# untitled.net
KiCad netlist of a schematic drawn in EAGLE
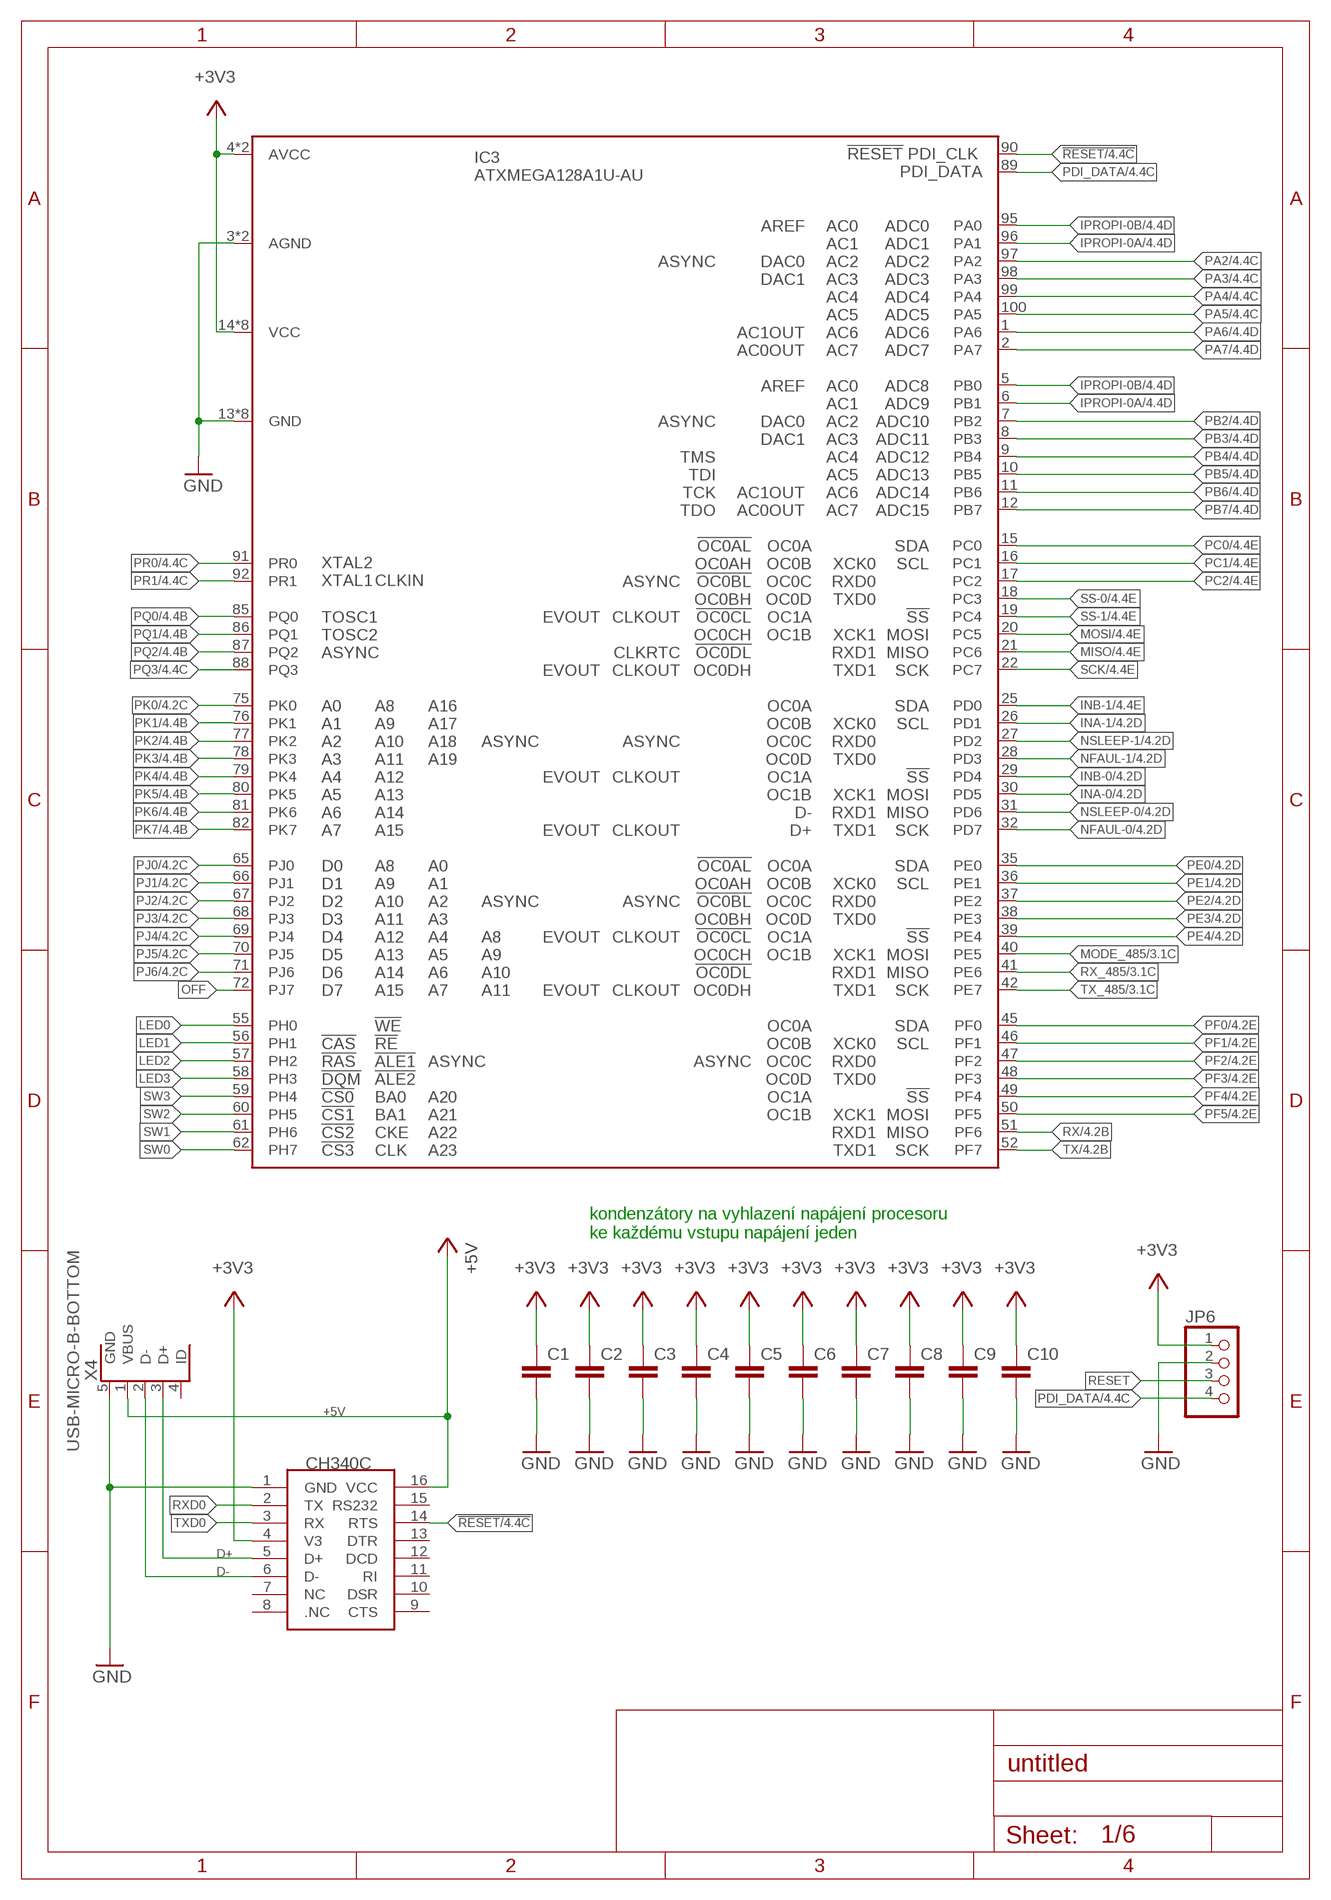
[diagram p0: schematic, sheet 1]
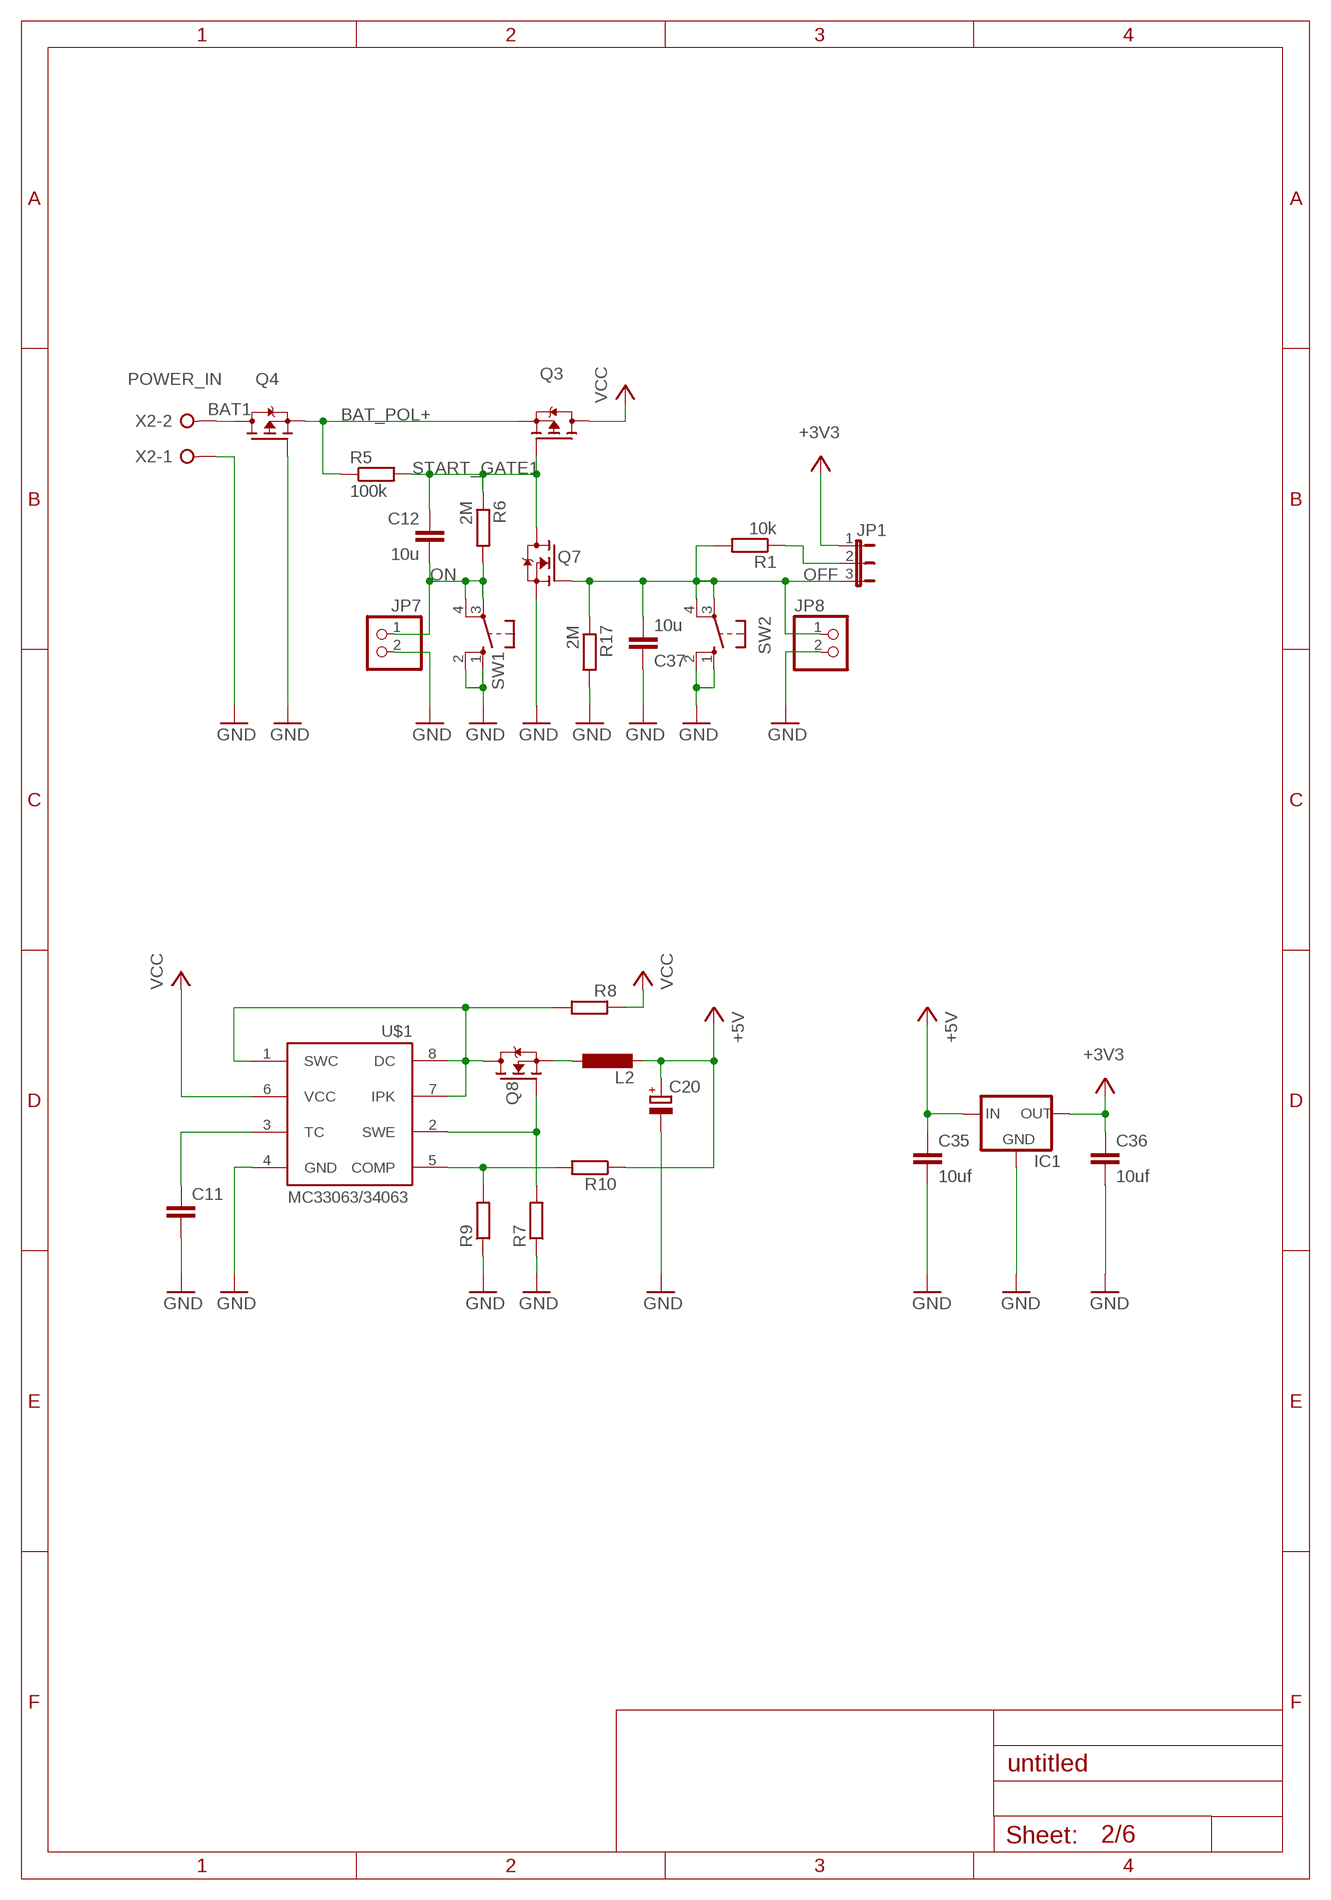
[diagram p1: schematic, sheet 2]
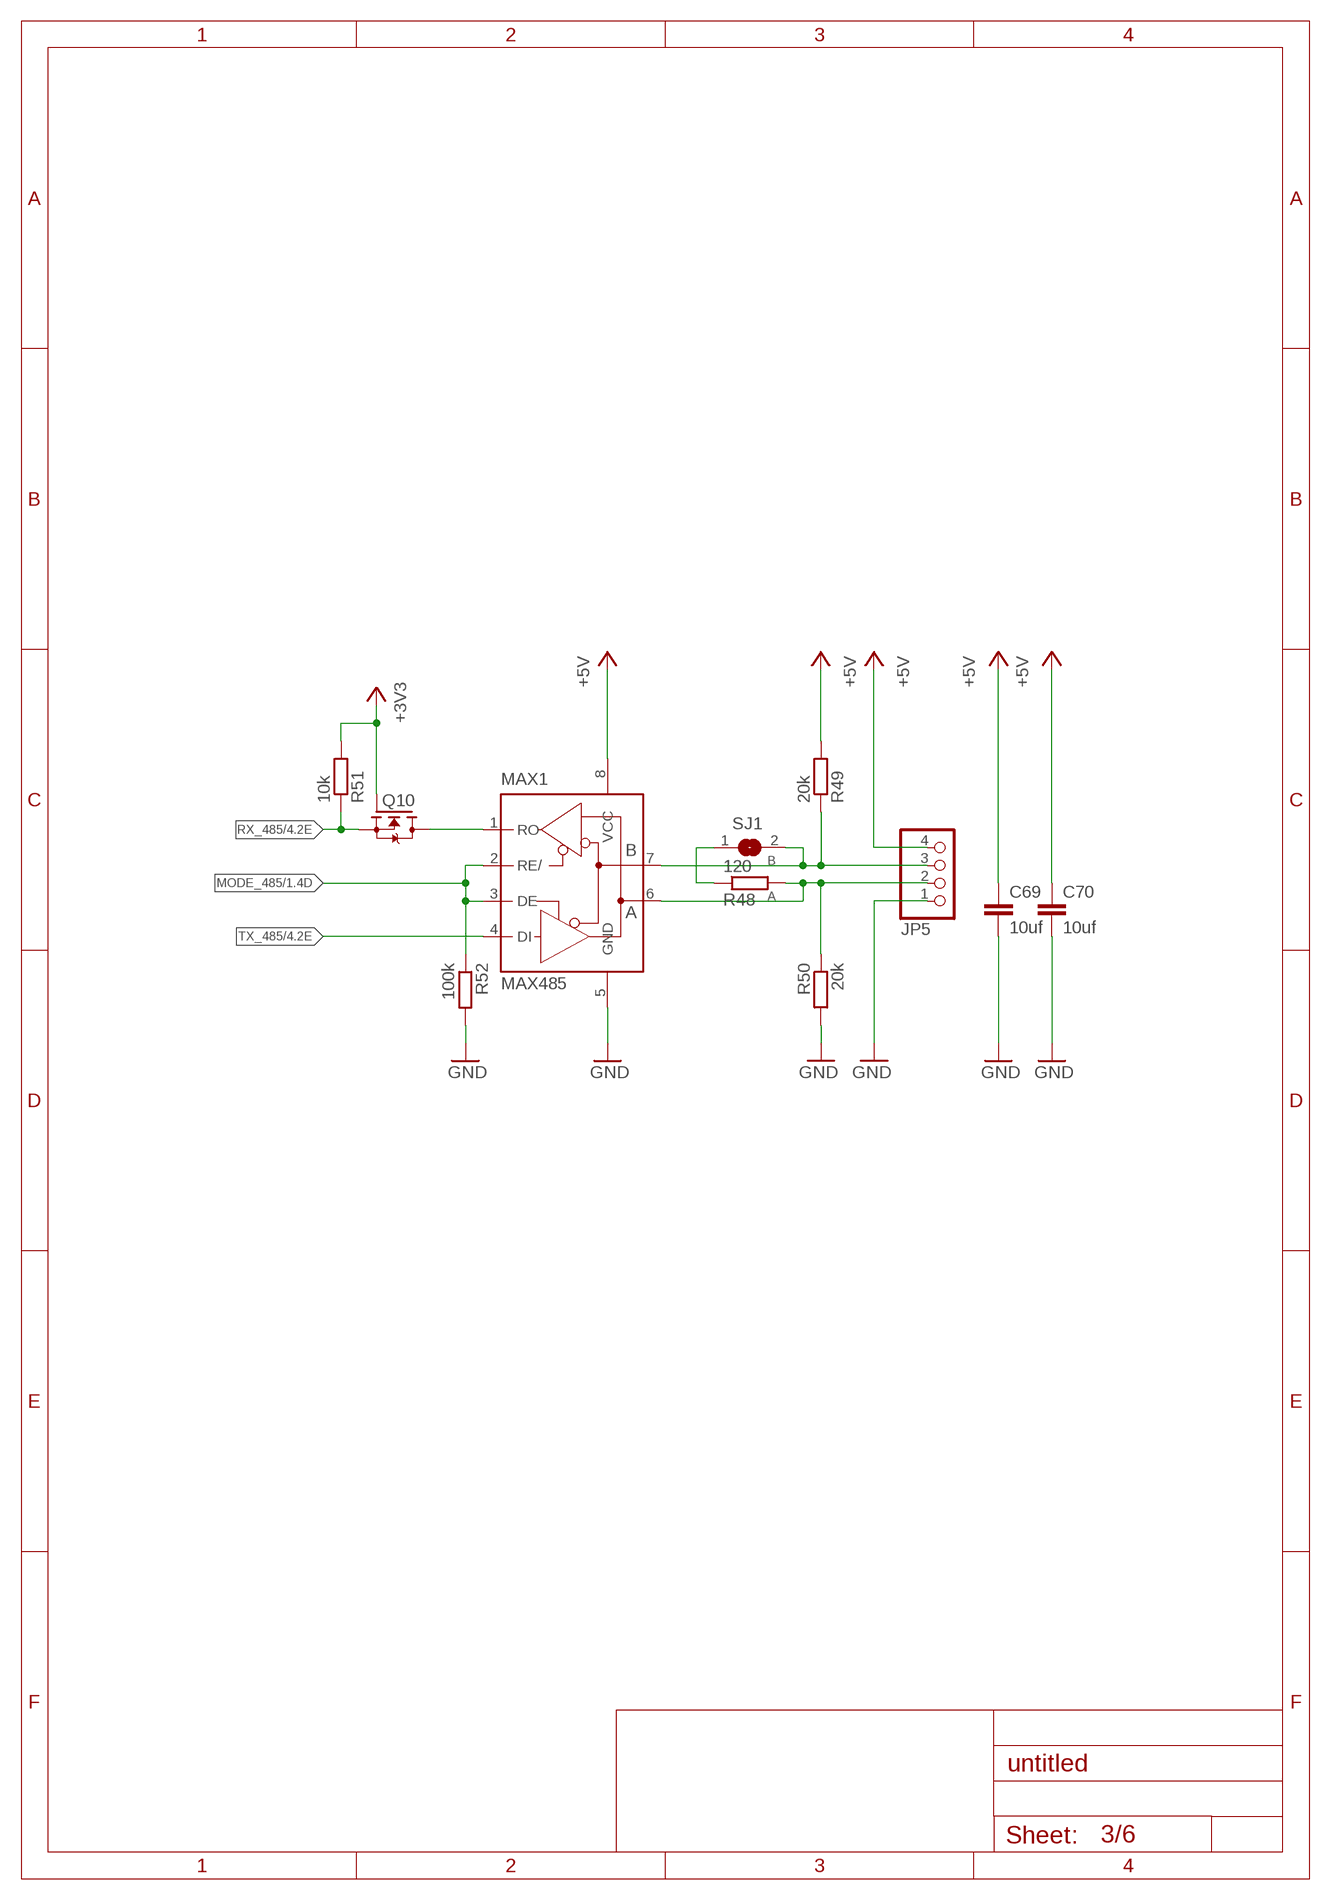
[diagram p2: schematic, sheet 3]
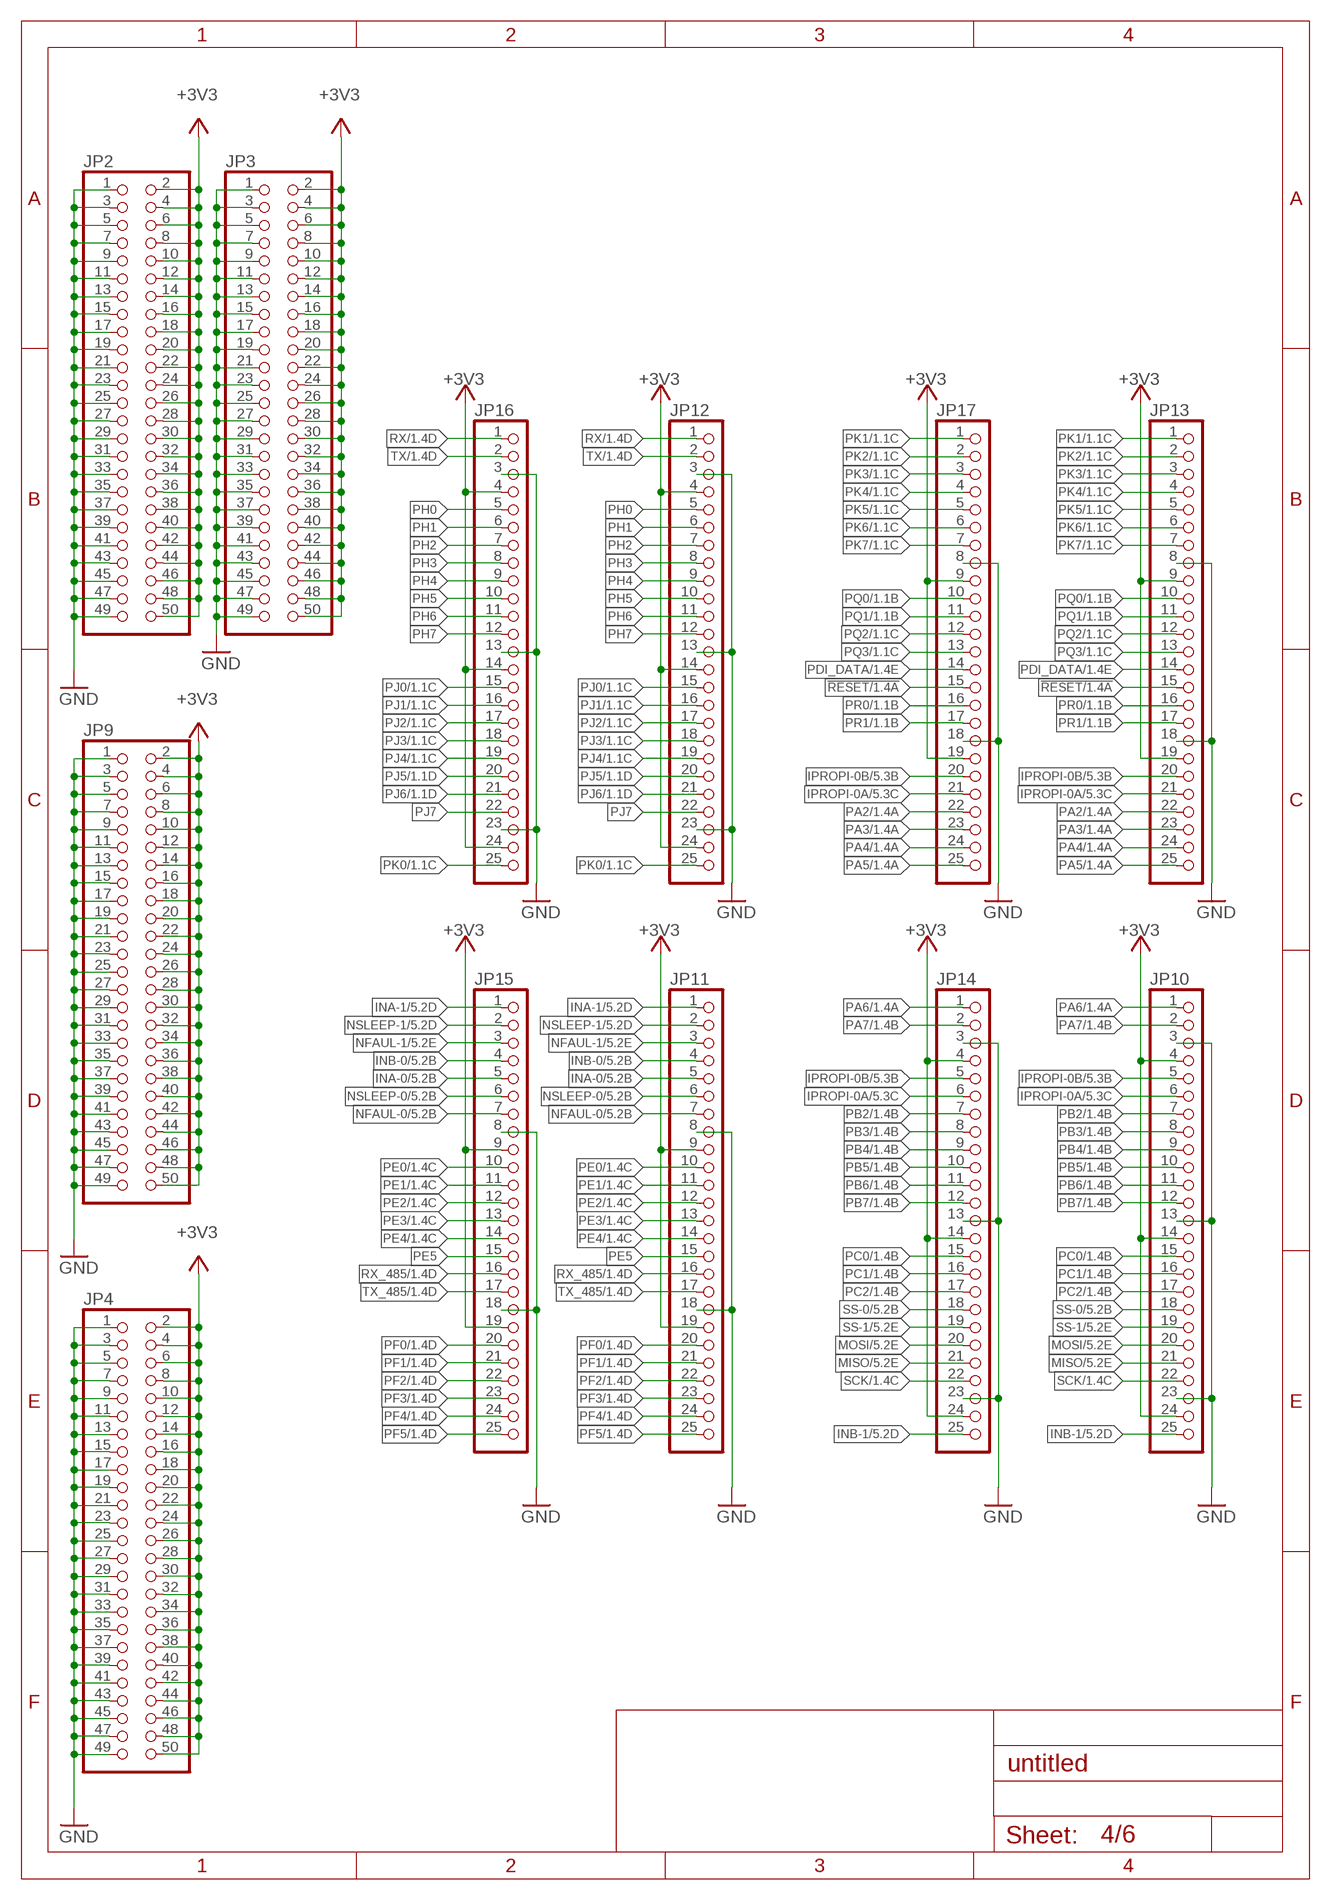
[diagram p3: schematic, sheet 4]
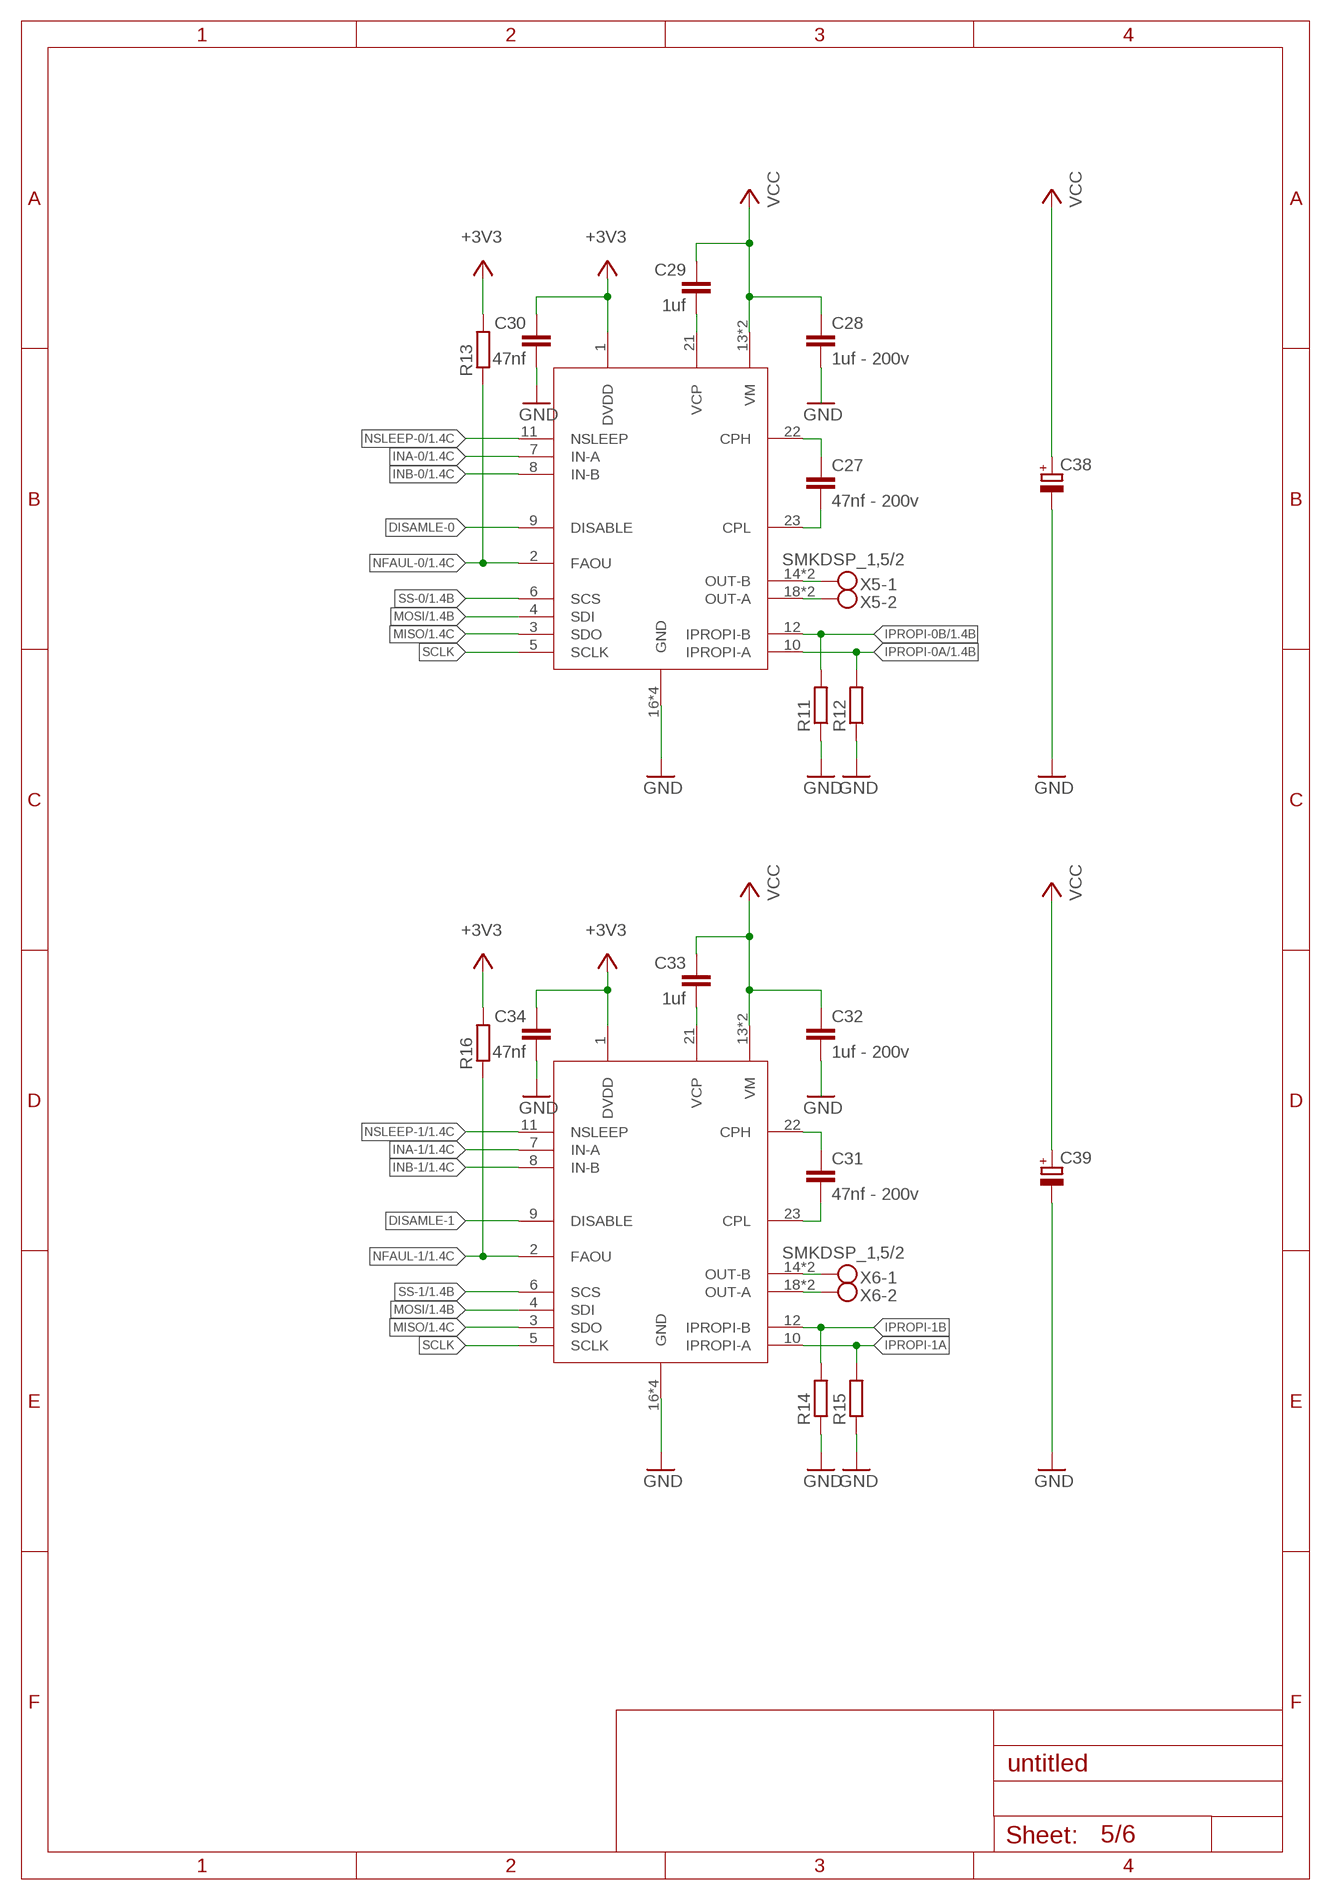
[diagram p4: schematic, sheet 5]
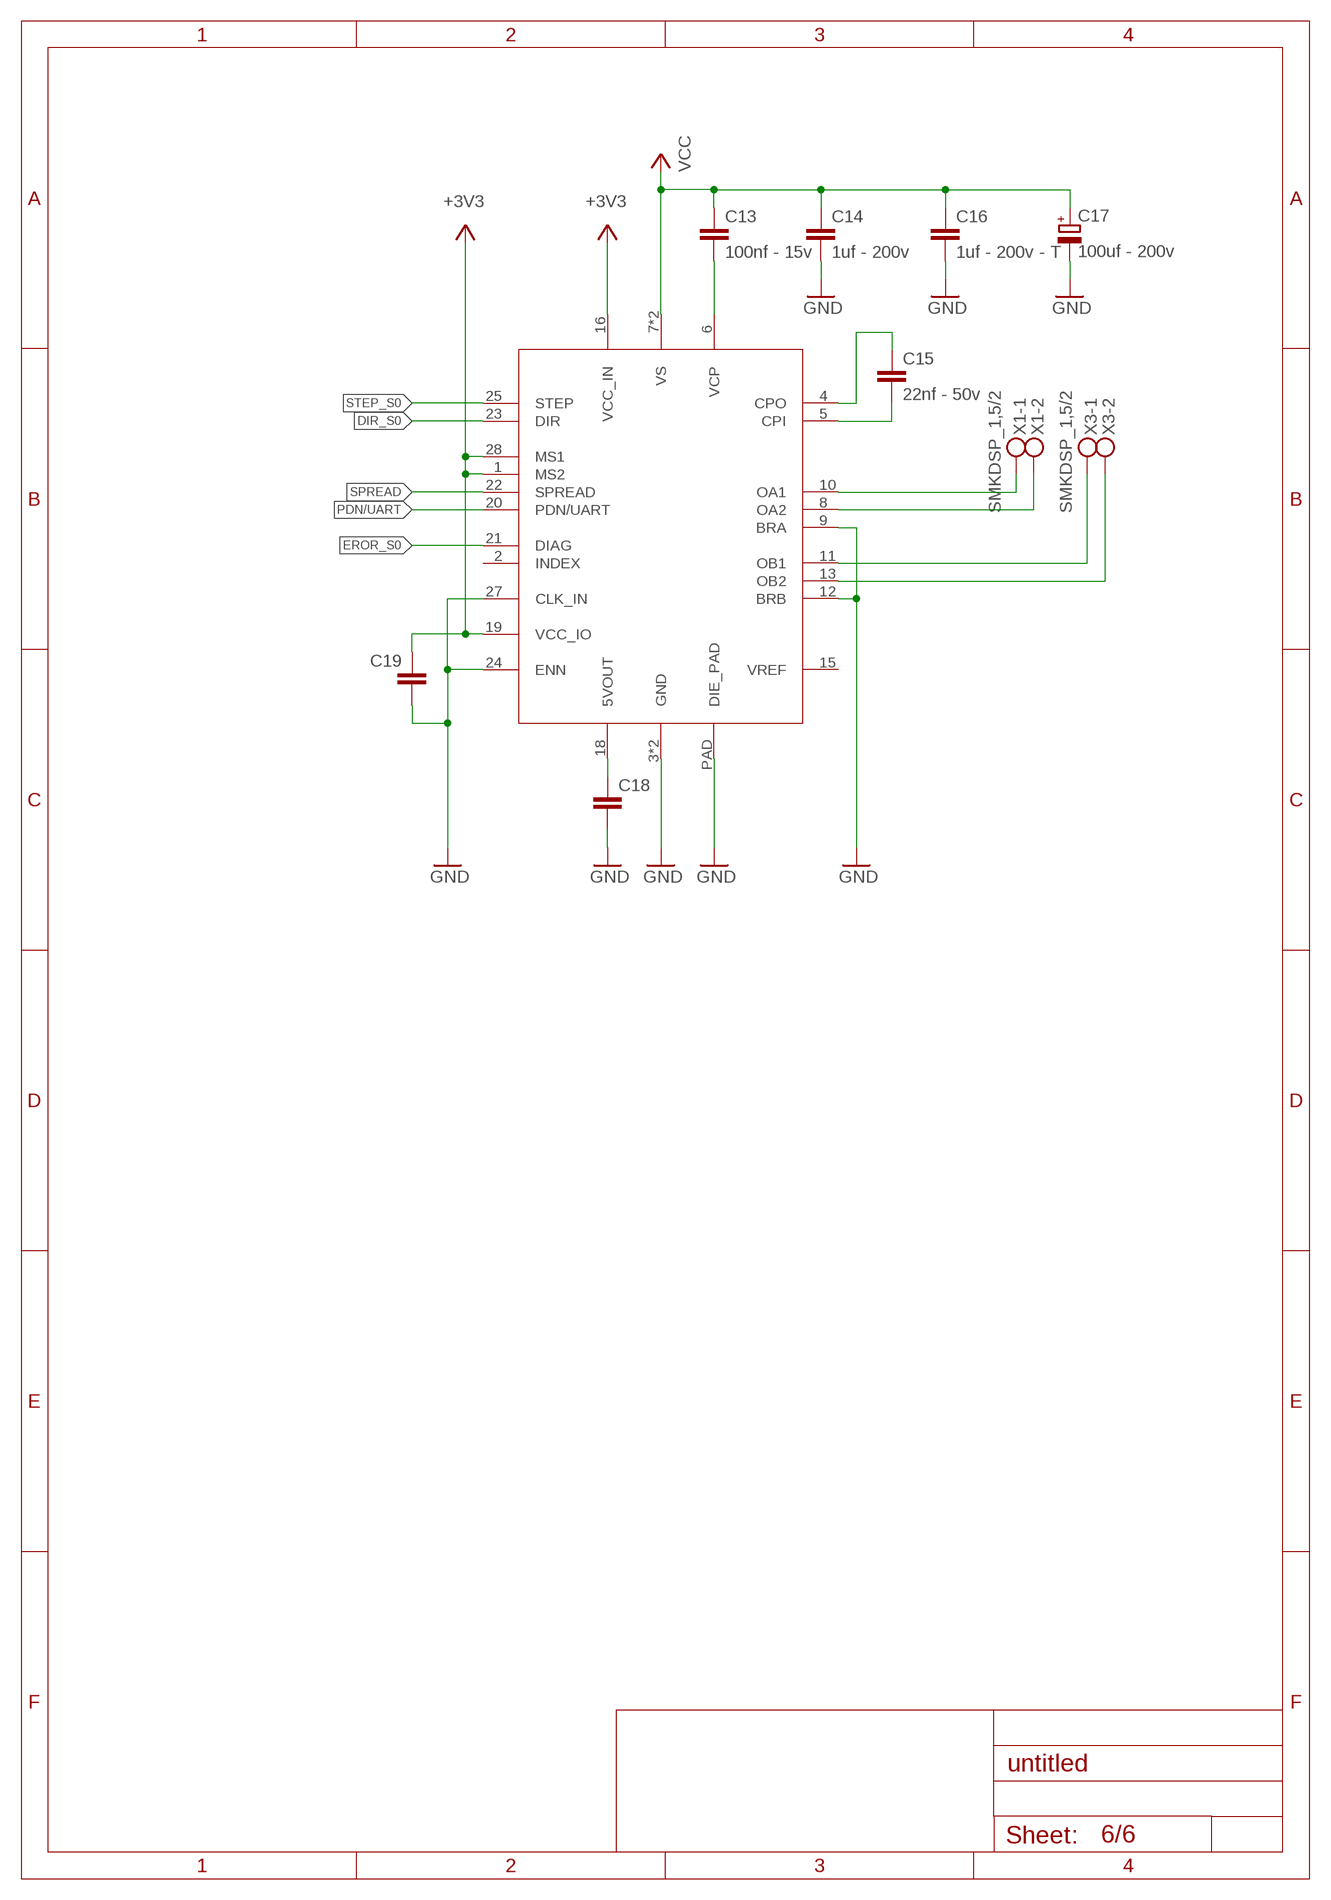
[diagram p5: schematic, sheet 6]

(export (version "E")
  (design (tool "Eeschema 10.0.6"))
  (components
    (comp (ref "C69")
      (value "10uf")
      (footprint "eagle-import:C0402K")
      (libsource (lib "eagle-import") (part "rcl_334_C-EUC0402K"))
    )
    (comp (ref "C70")
      (value "10uf")
      (footprint "eagle-import:C0402K")
      (libsource (lib "eagle-import") (part "rcl_334_C-EUC0402K"))
    )
    (comp (ref "JP5")
      (value "PINHD-1X4")
      (footprint "eagle-import:1X04")
      (libsource (lib "eagle-import") (part "PINHD-1X4"))
    )
    (comp (ref "MAX1")
      (value "MAX485")
      (footprint "eagle-import:SO08")
      (libsource (lib "eagle-import") (part "MAX485"))
    )
    (comp (ref "Q10")
      (value "N-MOSFET-SOT23-GSD")
      (footprint "eagle-import:SOT23")
      (libsource (lib "eagle-import") (part "N-MOSFET-SOT23-GSD"))
    )
    (comp (ref "R48")
      (value "120")
      (footprint "eagle-import:R0402")
      (libsource (lib "eagle-import") (part "R-EU_R0402"))
    )
    (comp (ref "R49")
      (value "20k")
      (footprint "eagle-import:R0402")
      (libsource (lib "eagle-import") (part "R-EU_R0402"))
    )
    (comp (ref "R50")
      (value "20k")
      (footprint "eagle-import:R0402")
      (libsource (lib "eagle-import") (part "R-EU_R0402"))
    )
    (comp (ref "R51")
      (value "10k")
      (footprint "eagle-import:R0402")
      (libsource (lib "eagle-import") (part "R-EU_R0402"))
    )
    (comp (ref "R52")
      (value "100k")
      (footprint "eagle-import:R0402")
      (libsource (lib "eagle-import") (part "R-EU_R0402"))
    )
    (comp (ref "SJ1") (value "SJ") (footprint "eagle-import:SJ") (libsource (lib "eagle-import") (part "SJ")))
    (comp (ref "C1")
      (value "C-EUC0402")
      (footprint "eagle-import:C0402")
      (libsource (lib "eagle-import") (part "C-EUC0402"))
    )
    (comp (ref "C2")
      (value "C-EUC0402")
      (footprint "eagle-import:C0402")
      (libsource (lib "eagle-import") (part "C-EUC0402"))
    )
    (comp (ref "C3")
      (value "C-EUC0402")
      (footprint "eagle-import:C0402")
      (libsource (lib "eagle-import") (part "C-EUC0402"))
    )
    (comp (ref "C4")
      (value "C-EUC0402")
      (footprint "eagle-import:C0402")
      (libsource (lib "eagle-import") (part "C-EUC0402"))
    )
    (comp (ref "C5")
      (value "C-EUC0402")
      (footprint "eagle-import:C0402")
      (libsource (lib "eagle-import") (part "C-EUC0402"))
    )
    (comp (ref "C6")
      (value "C-EUC0402")
      (footprint "eagle-import:C0402")
      (libsource (lib "eagle-import") (part "C-EUC0402"))
    )
    (comp (ref "C7")
      (value "C-EUC0402")
      (footprint "eagle-import:C0402")
      (libsource (lib "eagle-import") (part "C-EUC0402"))
    )
    (comp (ref "C8")
      (value "C-EUC0402")
      (footprint "eagle-import:C0402")
      (libsource (lib "eagle-import") (part "C-EUC0402"))
    )
    (comp (ref "C9")
      (value "C-EUC0402")
      (footprint "eagle-import:C0402")
      (libsource (lib "eagle-import") (part "C-EUC0402"))
    )
    (comp (ref "C10")
      (value "C-EUC0402")
      (footprint "eagle-import:C0402")
      (libsource (lib "eagle-import") (part "C-EUC0402"))
    )
    (comp (ref "CH2")
      (value "CH340C")
      (footprint "eagle-import:SOIC16")
      (libsource (lib "eagle-import") (part "CH340C"))
    )
    (comp (ref "IC3")
      (value "ATXMEGA128A1U-AU")
      (footprint "eagle-import:TQFP100")
      (libsource (lib "eagle-import") (part "ATXMEGAA1U-AU128"))
    )
    (comp (ref "JP6")
      (value "PINHD-1X4")
      (footprint "eagle-import:1X04")
      (libsource (lib "eagle-import") (part "PINHD-1X4"))
    )
    (comp (ref "X4")
      (value "USB-MICRO-B-BOTTOM")
      (footprint "eagle-import:USB-MICRO-B-BOTTOM-MOLEX")
      (libsource (lib "eagle-import") (part "USB-MICRO-B-BOTTOM"))
    )
    (comp (ref "C13")
      (value "100nf - 15v")
      (footprint "eagle-import:C1206")
      (libsource (lib "eagle-import") (part "rcl_334_C-EUC1206"))
    )
    (comp (ref "C14")
      (value "1uf - 200v")
      (footprint "eagle-import:C1206")
      (libsource (lib "eagle-import") (part "rcl_334_C-EUC1206"))
    )
    (comp (ref "C15")
      (value "22nf - 50v")
      (footprint "eagle-import:C1206")
      (libsource (lib "eagle-import") (part "rcl_334_C-EUC1206"))
    )
    (comp (ref "C16")
      (value "1uf - 200v - T")
      (footprint "eagle-import:C1206")
      (libsource (lib "eagle-import") (part "rcl_334_C-EUC1206"))
    )
    (comp (ref "C17")
      (value "100uf - 200v")
      (footprint "eagle-import:E5-10,5")
      (libsource (lib "eagle-import") (part "CPOL-EUE5-10.5"))
    )
    (comp (ref "C18")
      (value "C-EUC0603")
      (footprint "eagle-import:C0603")
      (libsource (lib "eagle-import") (part "C-EUC0603"))
    )
    (comp (ref "C19")
      (value "C-EUC0402")
      (footprint "eagle-import:C0402")
      (libsource (lib "eagle-import") (part "C-EUC0402"))
    )
    (comp (ref "S0")
      (value "TMC2224")
      (footprint "eagle-import:QFN28")
      (libsource (lib "eagle-import") (part "TMC2224"))
    )
    (comp (ref "X1")
      (value "SMKDSP_1,5/2")
      (footprint "eagle-import:SMKDSP_1,5_2")
      (fields (field (name "MF") "FARNELL") (field (name "MPN") "1733570"))
      (libsource (lib "eagle-import") (part "SMKDSP_1,5/2"))
    )
    (comp (ref "X3")
      (value "SMKDSP_1,5/2")
      (footprint "eagle-import:SMKDSP_1,5_2")
      (fields (field (name "MF") "FARNELL") (field (name "MPN") "1733570"))
      (libsource (lib "eagle-import") (part "SMKDSP_1,5/2"))
    )
    (comp (ref "JP2")
      (value "PINHD-2X25")
      (footprint "eagle-import:2X25")
      (libsource (lib "eagle-import") (part "PINHD-2X25"))
    )
    (comp (ref "JP3")
      (value "PINHD-2X25")
      (footprint "eagle-import:2X25")
      (libsource (lib "eagle-import") (part "PINHD-2X25"))
    )
    (comp (ref "JP4")
      (value "PINHD-2X25")
      (footprint "eagle-import:2X25")
      (libsource (lib "eagle-import") (part "PINHD-2X25"))
    )
    (comp (ref "JP9")
      (value "PINHD-2X25")
      (footprint "eagle-import:2X25")
      (libsource (lib "eagle-import") (part "PINHD-2X25"))
    )
    (comp (ref "JP10")
      (value "PINHD-1X25")
      (footprint "eagle-import:1X25")
      (libsource (lib "eagle-import") (part "PINHD-1X25"))
    )
    (comp (ref "JP11")
      (value "PINHD-1X25")
      (footprint "eagle-import:1X25")
      (libsource (lib "eagle-import") (part "PINHD-1X25"))
    )
    (comp (ref "JP12")
      (value "PINHD-1X25")
      (footprint "eagle-import:1X25")
      (libsource (lib "eagle-import") (part "PINHD-1X25"))
    )
    (comp (ref "JP13")
      (value "PINHD-1X25")
      (footprint "eagle-import:1X25")
      (libsource (lib "eagle-import") (part "PINHD-1X25"))
    )
    (comp (ref "JP14")
      (value "PINHD-1X25")
      (footprint "eagle-import:1X25")
      (libsource (lib "eagle-import") (part "PINHD-1X25"))
    )
    (comp (ref "JP15")
      (value "PINHD-1X25")
      (footprint "eagle-import:1X25")
      (libsource (lib "eagle-import") (part "PINHD-1X25"))
    )
    (comp (ref "JP16")
      (value "PINHD-1X25")
      (footprint "eagle-import:1X25")
      (libsource (lib "eagle-import") (part "PINHD-1X25"))
    )
    (comp (ref "JP17")
      (value "PINHD-1X25")
      (footprint "eagle-import:1X25")
      (libsource (lib "eagle-import") (part "PINHD-1X25"))
    )
    (comp (ref "C27")
      (value "47nf - 200v")
      (footprint "eagle-import:C0603")
      (libsource (lib "eagle-import") (part "rcl_334_C-EUC0603"))
    )
    (comp (ref "C28")
      (value "1uf - 200v")
      (footprint "eagle-import:C1206")
      (libsource (lib "eagle-import") (part "rcl_334_C-EUC1206"))
    )
    (comp (ref "C29")
      (value "1uf")
      (footprint "eagle-import:C1206")
      (libsource (lib "eagle-import") (part "rcl_334_C-EUC1206"))
    )
    (comp (ref "C30")
      (value "47nf")
      (footprint "eagle-import:C1206")
      (libsource (lib "eagle-import") (part "rcl_334_C-EUC1206"))
    )
    (comp (ref "C31")
      (value "47nf - 200v")
      (footprint "eagle-import:C0603")
      (libsource (lib "eagle-import") (part "rcl_334_C-EUC0603"))
    )
    (comp (ref "C32")
      (value "1uf - 200v")
      (footprint "eagle-import:C1206")
      (libsource (lib "eagle-import") (part "rcl_334_C-EUC1206"))
    )
    (comp (ref "C33")
      (value "1uf")
      (footprint "eagle-import:C1206")
      (libsource (lib "eagle-import") (part "rcl_334_C-EUC1206"))
    )
    (comp (ref "C34")
      (value "47nf")
      (footprint "eagle-import:C1206")
      (libsource (lib "eagle-import") (part "rcl_334_C-EUC1206"))
    )
    (comp (ref "C38")
      (value "CPOL-EUE5-10.5")
      (footprint "eagle-import:E5-10,5")
      (libsource (lib "eagle-import") (part "CPOL-EUE5-10.5"))
    )
    (comp (ref "C39")
      (value "CPOL-EUE5-10.5")
      (footprint "eagle-import:E5-10,5")
      (libsource (lib "eagle-import") (part "CPOL-EUE5-10.5"))
    )
    (comp (ref "R11")
      (value "R-EU_R0603")
      (footprint "eagle-import:R0603")
      (libsource (lib "eagle-import") (part "R-EU_R0603"))
    )
    (comp (ref "R12")
      (value "R-EU_R0603")
      (footprint "eagle-import:R0603")
      (libsource (lib "eagle-import") (part "R-EU_R0603"))
    )
    (comp (ref "R13")
      (value "R-EU_R0603")
      (footprint "eagle-import:R0603")
      (libsource (lib "eagle-import") (part "R-EU_R0603"))
    )
    (comp (ref "R14")
      (value "R-EU_R0603")
      (footprint "eagle-import:R0603")
      (libsource (lib "eagle-import") (part "R-EU_R0603"))
    )
    (comp (ref "R15")
      (value "R-EU_R0603")
      (footprint "eagle-import:R0603")
      (libsource (lib "eagle-import") (part "R-EU_R0603"))
    )
    (comp (ref "R16")
      (value "R-EU_R0603")
      (footprint "eagle-import:R0603")
      (libsource (lib "eagle-import") (part "R-EU_R0603"))
    )
    (comp (ref "U$2")
      (value "DER8873")
      (footprint "eagle-import:24HTSSOP")
      (libsource (lib "eagle-import") (part "DER8873"))
    )
    (comp (ref "U$6")
      (value "DER8873")
      (footprint "eagle-import:24HTSSOP")
      (libsource (lib "eagle-import") (part "DER8873"))
    )
    (comp (ref "X5")
      (value "SMKDSP_1,5/2")
      (footprint "eagle-import:SMKDSP_1,5_2")
      (fields (field (name "MF") "FARNELL") (field (name "MPN") "1733570"))
      (libsource (lib "eagle-import") (part "SMKDSP_1,5/2"))
    )
    (comp (ref "X6")
      (value "SMKDSP_1,5/2")
      (footprint "eagle-import:SMKDSP_1,5_2")
      (fields (field (name "MF") "FARNELL") (field (name "MPN") "1733570"))
      (libsource (lib "eagle-import") (part "SMKDSP_1,5/2"))
    )
    (comp (ref "C11")
      (value "C-EUC0603")
      (footprint "eagle-import:C0603")
      (libsource (lib "eagle-import") (part "rcl_334_C-EUC0603"))
    )
    (comp (ref "C12")
      (value "10u")
      (footprint "eagle-import:C1206")
      (libsource (lib "eagle-import") (part "rcl_upravena_C-EUC1206"))
    )
    (comp (ref "C20")
      (value "CPOL-EUD")
      (footprint "eagle-import:PANASONIC_D")
      (libsource (lib "eagle-import") (part "rcl_334_CPOL-EUD"))
    )
    (comp (ref "C35")
      (value "10uf")
      (footprint "eagle-import:C0805")
      (libsource (lib "eagle-import") (part "C-EUC0805"))
    )
    (comp (ref "C36")
      (value "10uf")
      (footprint "eagle-import:C0805")
      (libsource (lib "eagle-import") (part "C-EUC0805"))
    )
    (comp (ref "C37")
      (value "10u")
      (footprint "eagle-import:C1206")
      (libsource (lib "eagle-import") (part "rcl_upravena_C-EUC1206"))
    )
    (comp (ref "IC1")
      (value "LM1117")
      (footprint "eagle-import:SOT223")
      (libsource (lib "eagle-import") (part "LM1117"))
    )
    (comp (ref "JP1")
      (value "JP2E")
      (footprint "eagle-import:JP2")
      (libsource (lib "eagle-import") (part "JP2E"))
    )
    (comp (ref "JP7")
      (value "PINHD-1X2")
      (footprint "eagle-import:1X02")
      (libsource (lib "eagle-import") (part "PINHD-1X2"))
    )
    (comp (ref "JP8")
      (value "PINHD-1X2")
      (footprint "eagle-import:1X02")
      (libsource (lib "eagle-import") (part "PINHD-1X2"))
    )
    (comp (ref "L2")
      (value "L-EUL3216C")
      (footprint "eagle-import:L3216C")
      (libsource (lib "eagle-import") (part "L-EUL3216C"))
    )
    (comp (ref "Q3")
      (value "P-MOSFET-MLP_HS")
      (footprint "eagle-import:MLP3.3X3.3_HS")
      (libsource (lib "eagle-import") (part "P-MOSFET-MLP_HS"))
    )
    (comp (ref "Q4")
      (value "P-MOSFET-MLP_HS")
      (footprint "eagle-import:MLP3.3X3.3_HS")
      (libsource (lib "eagle-import") (part "P-MOSFET-MLP_HS"))
    )
    (comp (ref "Q7")
      (value "N-MOSFET-SOT23-GSD")
      (footprint "eagle-import:SOT23")
      (libsource (lib "eagle-import") (part "N-MOSFET-SOT23-GSD"))
    )
    (comp (ref "Q8")
      (value "N-MOSFET-SOT23-GSD")
      (footprint "eagle-import:SOT23")
      (libsource (lib "eagle-import") (part "N-MOSFET-SOT23-GSD"))
    )
    (comp (ref "R1")
      (value "10k")
      (footprint "eagle-import:R0805")
      (libsource (lib "eagle-import") (part "rcl_upravena_R-EU_R0805"))
    )
    (comp (ref "R5")
      (value "100k")
      (footprint "eagle-import:R0805")
      (libsource (lib "eagle-import") (part "rcl_upravena_R-EU_R0805"))
    )
    (comp (ref "R6")
      (value "2M")
      (footprint "eagle-import:M0805")
      (libsource (lib "eagle-import") (part "rcl_upravena_R-EU_M0805"))
    )
    (comp (ref "R7")
      (value "R-EU_R0603")
      (footprint "eagle-import:R0603")
      (libsource (lib "eagle-import") (part "R-EU_R0603"))
    )
    (comp (ref "R8")
      (value "R-EU_R0603")
      (footprint "eagle-import:R0603")
      (libsource (lib "eagle-import") (part "R-EU_R0603"))
    )
    (comp (ref "R9")
      (value "R-EU_R0603")
      (footprint "eagle-import:R0603")
      (libsource (lib "eagle-import") (part "R-EU_R0603"))
    )
    (comp (ref "R10")
      (value "R-EU_R0603")
      (footprint "eagle-import:R0603")
      (libsource (lib "eagle-import") (part "R-EU_R0603"))
    )
    (comp (ref "R17")
      (value "2M")
      (footprint "eagle-import:M0805")
      (libsource (lib "eagle-import") (part "rcl_upravena_R-EU_M0805"))
    )
    (comp (ref "SW1")
      (value "10-XX")
      (footprint "eagle-import:B3F-10XX")
      (fields (field (name "MPN") "B3F-1000"))
      (libsource (lib "eagle-import") (part "10-XX"))
    )
    (comp (ref "SW2")
      (value "10-XX")
      (footprint "eagle-import:B3F-10XX")
      (fields (field (name "MPN") "B3F-1000"))
      (libsource (lib "eagle-import") (part "10-XX"))
    )
    (comp (ref "U$1")
      (value "MC33063/MC34063D")
      (footprint "eagle-import:SO08")
      (libsource (lib "eagle-import") (part "MC33063/MC34063D"))
    )
    (comp (ref "X2")
      (value "POWER_IN")
      (footprint "eagle-import:W237-132")
      (libsource (lib "eagle-import") (part "W237-02P"))
    )
  )
  (nets
    (net (code "1") (name "+3V3") (class "Default")
      (node (ref "C1") (pin "1") (pinfunction "1_1") (pintype "passive"))
      (node (ref "C10") (pin "1") (pinfunction "1_1") (pintype "passive"))
      (node (ref "C19") (pin "1") (pinfunction "1_1") (pintype "passive"))
      (node (ref "C2") (pin "1") (pinfunction "1_1") (pintype "passive"))
      (node (ref "C3") (pin "1") (pinfunction "1_1") (pintype "passive"))
      (node (ref "C30") (pin "1") (pinfunction "1_1") (pintype "passive"))
      (node (ref "C34") (pin "1") (pinfunction "1_1") (pintype "passive"))
      (node (ref "C36") (pin "1") (pinfunction "1_1") (pintype "passive"))
      (node (ref "C4") (pin "1") (pinfunction "1_1") (pintype "passive"))
      (node (ref "C5") (pin "1") (pinfunction "1_1") (pintype "passive"))
      (node (ref "C6") (pin "1") (pinfunction "1_1") (pintype "passive"))
      (node (ref "C7") (pin "1") (pinfunction "1_1") (pintype "passive"))
      (node (ref "C8") (pin "1") (pinfunction "1_1") (pintype "passive"))
      (node (ref "C9") (pin "1") (pinfunction "1_1") (pintype "passive"))
      (node (ref "CH2") (pin "4") (pinfunction "V3_4") (pintype "bidirectional"))
      (node (ref "IC1") (pin "2") (pinfunction "OUT_2") (pintype "passive"))
      (node (ref "IC3") (pin "14") (pinfunction "VCC_14") (pintype "power_in"))
      (node (ref "IC3") (pin "24") (pinfunction "VCC_24") (pintype "power_in"))
      (node (ref "IC3") (pin "34") (pinfunction "VCC_34") (pintype "power_in"))
      (node (ref "IC3") (pin "4") (pinfunction "AVCC_4") (pintype "power_in"))
      (node (ref "IC3") (pin "44") (pinfunction "VCC_44") (pintype "power_in"))
      (node (ref "IC3") (pin "54") (pinfunction "VCC_54") (pintype "power_in"))
      (node (ref "IC3") (pin "64") (pinfunction "VCC_64") (pintype "power_in"))
      (node (ref "IC3") (pin "74") (pinfunction "VCC_74") (pintype "power_in"))
      (node (ref "IC3") (pin "83") (pinfunction "VCC_83") (pintype "power_in"))
      (node (ref "IC3") (pin "94") (pinfunction "AVCC_94") (pintype "power_in"))
      (node (ref "JP1") (pin "1") (pinfunction "1_1") (pintype "passive"))
      (node (ref "JP10") (pin "14") (pinfunction "14_14") (pintype "passive"))
      (node (ref "JP10") (pin "24") (pinfunction "24_24") (pintype "passive"))
      (node (ref "JP10") (pin "4") (pinfunction "4_4") (pintype "passive"))
      (node (ref "JP11") (pin "19") (pinfunction "19_19") (pintype "passive"))
      (node (ref "JP11") (pin "9") (pinfunction "9_9") (pintype "passive"))
      (node (ref "JP12") (pin "14") (pinfunction "14_14") (pintype "passive"))
      (node (ref "JP12") (pin "24") (pinfunction "24_24") (pintype "passive"))
      (node (ref "JP12") (pin "4") (pinfunction "4_4") (pintype "passive"))
      (node (ref "JP13") (pin "19") (pinfunction "19_19") (pintype "passive"))
      (node (ref "JP13") (pin "9") (pinfunction "9_9") (pintype "passive"))
      (node (ref "JP14") (pin "14") (pinfunction "14_14") (pintype "passive"))
      (node (ref "JP14") (pin "24") (pinfunction "24_24") (pintype "passive"))
      (node (ref "JP14") (pin "4") (pinfunction "4_4") (pintype "passive"))
      (node (ref "JP15") (pin "19") (pinfunction "19_19") (pintype "passive"))
      (node (ref "JP15") (pin "9") (pinfunction "9_9") (pintype "passive"))
      (node (ref "JP16") (pin "14") (pinfunction "14_14") (pintype "passive"))
      (node (ref "JP16") (pin "24") (pinfunction "24_24") (pintype "passive"))
      (node (ref "JP16") (pin "4") (pinfunction "4_4") (pintype "passive"))
      (node (ref "JP17") (pin "19") (pinfunction "19_19") (pintype "passive"))
      (node (ref "JP17") (pin "9") (pinfunction "9_9") (pintype "passive"))
      (node (ref "JP2") (pin "10") (pinfunction "10_10") (pintype "passive"))
      (node (ref "JP2") (pin "12") (pinfunction "12_12") (pintype "passive"))
      (node (ref "JP2") (pin "14") (pinfunction "14_14") (pintype "passive"))
      (node (ref "JP2") (pin "16") (pinfunction "16_16") (pintype "passive"))
      (node (ref "JP2") (pin "18") (pinfunction "18_18") (pintype "passive"))
      (node (ref "JP2") (pin "2") (pinfunction "2_2") (pintype "passive"))
      (node (ref "JP2") (pin "20") (pinfunction "20_20") (pintype "passive"))
      (node (ref "JP2") (pin "22") (pinfunction "22_22") (pintype "passive"))
      (node (ref "JP2") (pin "24") (pinfunction "24_24") (pintype "passive"))
      (node (ref "JP2") (pin "26") (pinfunction "26_26") (pintype "passive"))
      (node (ref "JP2") (pin "28") (pinfunction "28_28") (pintype "passive"))
      (node (ref "JP2") (pin "30") (pinfunction "30_30") (pintype "passive"))
      (node (ref "JP2") (pin "32") (pinfunction "32_32") (pintype "passive"))
      (node (ref "JP2") (pin "34") (pinfunction "34_34") (pintype "passive"))
      (node (ref "JP2") (pin "36") (pinfunction "36_36") (pintype "passive"))
      (node (ref "JP2") (pin "38") (pinfunction "38_38") (pintype "passive"))
      (node (ref "JP2") (pin "4") (pinfunction "4_4") (pintype "passive"))
      (node (ref "JP2") (pin "40") (pinfunction "40_40") (pintype "passive"))
      (node (ref "JP2") (pin "42") (pinfunction "42_42") (pintype "passive"))
      (node (ref "JP2") (pin "44") (pinfunction "44_44") (pintype "passive"))
      (node (ref "JP2") (pin "46") (pinfunction "46_46") (pintype "passive"))
      (node (ref "JP2") (pin "48") (pinfunction "48_48") (pintype "passive"))
      (node (ref "JP2") (pin "50") (pinfunction "50_50") (pintype "passive"))
      (node (ref "JP2") (pin "6") (pinfunction "6_6") (pintype "passive"))
      (node (ref "JP2") (pin "8") (pinfunction "8_8") (pintype "passive"))
      (node (ref "JP3") (pin "10") (pinfunction "10_10") (pintype "passive"))
      (node (ref "JP3") (pin "12") (pinfunction "12_12") (pintype "passive"))
      (node (ref "JP3") (pin "14") (pinfunction "14_14") (pintype "passive"))
      (node (ref "JP3") (pin "16") (pinfunction "16_16") (pintype "passive"))
      (node (ref "JP3") (pin "18") (pinfunction "18_18") (pintype "passive"))
      (node (ref "JP3") (pin "2") (pinfunction "2_2") (pintype "passive"))
      (node (ref "JP3") (pin "20") (pinfunction "20_20") (pintype "passive"))
      (node (ref "JP3") (pin "22") (pinfunction "22_22") (pintype "passive"))
      (node (ref "JP3") (pin "24") (pinfunction "24_24") (pintype "passive"))
      (node (ref "JP3") (pin "26") (pinfunction "26_26") (pintype "passive"))
      (node (ref "JP3") (pin "28") (pinfunction "28_28") (pintype "passive"))
      (node (ref "JP3") (pin "30") (pinfunction "30_30") (pintype "passive"))
      (node (ref "JP3") (pin "32") (pinfunction "32_32") (pintype "passive"))
      (node (ref "JP3") (pin "34") (pinfunction "34_34") (pintype "passive"))
      (node (ref "JP3") (pin "36") (pinfunction "36_36") (pintype "passive"))
      (node (ref "JP3") (pin "38") (pinfunction "38_38") (pintype "passive"))
      (node (ref "JP3") (pin "4") (pinfunction "4_4") (pintype "passive"))
      (node (ref "JP3") (pin "40") (pinfunction "40_40") (pintype "passive"))
      (node (ref "JP3") (pin "42") (pinfunction "42_42") (pintype "passive"))
      (node (ref "JP3") (pin "44") (pinfunction "44_44") (pintype "passive"))
      (node (ref "JP3") (pin "46") (pinfunction "46_46") (pintype "passive"))
      (node (ref "JP3") (pin "48") (pinfunction "48_48") (pintype "passive"))
      (node (ref "JP3") (pin "50") (pinfunction "50_50") (pintype "passive"))
      (node (ref "JP3") (pin "6") (pinfunction "6_6") (pintype "passive"))
      (node (ref "JP3") (pin "8") (pinfunction "8_8") (pintype "passive"))
      (node (ref "JP4") (pin "10") (pinfunction "10_10") (pintype "passive"))
      (node (ref "JP4") (pin "12") (pinfunction "12_12") (pintype "passive"))
      (node (ref "JP4") (pin "14") (pinfunction "14_14") (pintype "passive"))
      (node (ref "JP4") (pin "16") (pinfunction "16_16") (pintype "passive"))
      (node (ref "JP4") (pin "18") (pinfunction "18_18") (pintype "passive"))
      (node (ref "JP4") (pin "2") (pinfunction "2_2") (pintype "passive"))
      (node (ref "JP4") (pin "20") (pinfunction "20_20") (pintype "passive"))
      (node (ref "JP4") (pin "22") (pinfunction "22_22") (pintype "passive"))
      (node (ref "JP4") (pin "24") (pinfunction "24_24") (pintype "passive"))
      (node (ref "JP4") (pin "26") (pinfunction "26_26") (pintype "passive"))
      (node (ref "JP4") (pin "28") (pinfunction "28_28") (pintype "passive"))
      (node (ref "JP4") (pin "30") (pinfunction "30_30") (pintype "passive"))
      (node (ref "JP4") (pin "32") (pinfunction "32_32") (pintype "passive"))
      (node (ref "JP4") (pin "34") (pinfunction "34_34") (pintype "passive"))
      (node (ref "JP4") (pin "36") (pinfunction "36_36") (pintype "passive"))
      (node (ref "JP4") (pin "38") (pinfunction "38_38") (pintype "passive"))
      (node (ref "JP4") (pin "4") (pinfunction "4_4") (pintype "passive"))
      (node (ref "JP4") (pin "40") (pinfunction "40_40") (pintype "passive"))
      (node (ref "JP4") (pin "42") (pinfunction "42_42") (pintype "passive"))
      (node (ref "JP4") (pin "44") (pinfunction "44_44") (pintype "passive"))
      (node (ref "JP4") (pin "46") (pinfunction "46_46") (pintype "passive"))
      (node (ref "JP4") (pin "48") (pinfunction "48_48") (pintype "passive"))
      (node (ref "JP4") (pin "50") (pinfunction "50_50") (pintype "passive"))
      (node (ref "JP4") (pin "6") (pinfunction "6_6") (pintype "passive"))
      (node (ref "JP4") (pin "8") (pinfunction "8_8") (pintype "passive"))
      (node (ref "JP6") (pin "1") (pinfunction "1_1") (pintype "passive"))
      (node (ref "JP9") (pin "10") (pinfunction "10_10") (pintype "passive"))
      (node (ref "JP9") (pin "12") (pinfunction "12_12") (pintype "passive"))
      (node (ref "JP9") (pin "14") (pinfunction "14_14") (pintype "passive"))
      (node (ref "JP9") (pin "16") (pinfunction "16_16") (pintype "passive"))
      (node (ref "JP9") (pin "18") (pinfunction "18_18") (pintype "passive"))
      (node (ref "JP9") (pin "2") (pinfunction "2_2") (pintype "passive"))
      (node (ref "JP9") (pin "20") (pinfunction "20_20") (pintype "passive"))
      (node (ref "JP9") (pin "22") (pinfunction "22_22") (pintype "passive"))
      (node (ref "JP9") (pin "24") (pinfunction "24_24") (pintype "passive"))
      (node (ref "JP9") (pin "26") (pinfunction "26_26") (pintype "passive"))
      (node (ref "JP9") (pin "28") (pinfunction "28_28") (pintype "passive"))
      (node (ref "JP9") (pin "30") (pinfunction "30_30") (pintype "passive"))
      (node (ref "JP9") (pin "32") (pinfunction "32_32") (pintype "passive"))
      (node (ref "JP9") (pin "34") (pinfunction "34_34") (pintype "passive"))
      (node (ref "JP9") (pin "36") (pinfunction "36_36") (pintype "passive"))
      (node (ref "JP9") (pin "38") (pinfunction "38_38") (pintype "passive"))
      (node (ref "JP9") (pin "4") (pinfunction "4_4") (pintype "passive"))
      (node (ref "JP9") (pin "40") (pinfunction "40_40") (pintype "passive"))
      (node (ref "JP9") (pin "42") (pinfunction "42_42") (pintype "passive"))
      (node (ref "JP9") (pin "44") (pinfunction "44_44") (pintype "passive"))
      (node (ref "JP9") (pin "46") (pinfunction "46_46") (pintype "passive"))
      (node (ref "JP9") (pin "48") (pinfunction "48_48") (pintype "passive"))
      (node (ref "JP9") (pin "50") (pinfunction "50_50") (pintype "passive"))
      (node (ref "JP9") (pin "6") (pinfunction "6_6") (pintype "passive"))
      (node (ref "JP9") (pin "8") (pinfunction "8_8") (pintype "passive"))
      (node (ref "Q10") (pin "1") (pinfunction "G_1") (pintype "passive"))
      (node (ref "R13") (pin "2") (pinfunction "2_2") (pintype "passive"))
      (node (ref "R16") (pin "2") (pinfunction "2_2") (pintype "passive"))
      (node (ref "R51") (pin "2") (pinfunction "2_2") (pintype "passive"))
      (node (ref "S0") (pin "1") (pinfunction "MS2_1") (pintype "bidirectional"))
      (node (ref "S0") (pin "16") (pinfunction "VCC_IN_16") (pintype "bidirectional"))
      (node (ref "S0") (pin "19") (pinfunction "VCC_IO_19") (pintype "bidirectional"))
      (node (ref "S0") (pin "28") (pinfunction "MS1_28") (pintype "bidirectional"))
      (node (ref "U$2") (pin "1") (pinfunction "DVDD_1") (pintype "bidirectional"))
      (node (ref "U$6") (pin "1") (pinfunction "DVDD_1") (pintype "bidirectional"))
    )
    (net (code "2") (name "+5V") (class "Default")
      (node (ref "C20") (pin "+") (pinfunction "+_+") (pintype "passive"))
      (node (ref "C35") (pin "1") (pinfunction "1_1") (pintype "passive"))
      (node (ref "C69") (pin "1") (pinfunction "1_1") (pintype "passive"))
      (node (ref "C70") (pin "1") (pinfunction "1_1") (pintype "passive"))
      (node (ref "CH2") (pin "16") (pinfunction "VCC_16") (pintype "bidirectional"))
      (node (ref "IC1") (pin "3") (pinfunction "IN_3") (pintype "input"))
      (node (ref "JP5") (pin "4") (pinfunction "4_4") (pintype "passive"))
      (node (ref "L2") (pin "2") (pinfunction "2_2") (pintype "passive"))
      (node (ref "MAX1") (pin "8") (pinfunction "VCC_8") (pintype "bidirectional"))
      (node (ref "R10") (pin "1") (pinfunction "1_1") (pintype "passive"))
      (node (ref "R49") (pin "2") (pinfunction "2_2") (pintype "passive"))
      (node (ref "X4") (pin "1") (pinfunction "VBUS_1") (pintype "passive"))
    )
    (net (code "3") (name "A") (class "Default")
      (node (ref "JP5") (pin "2") (pinfunction "2_2") (pintype "passive"))
      (node (ref "MAX1") (pin "6") (pinfunction "A_6") (pintype "passive"))
      (node (ref "R48") (pin "2") (pinfunction "2_2") (pintype "passive"))
      (node (ref "R50") (pin "1") (pinfunction "1_1") (pintype "passive"))
    )
    (net (code "4") (name "B") (class "Default")
      (node (ref "JP5") (pin "3") (pinfunction "3_3") (pintype "passive"))
      (node (ref "MAX1") (pin "7") (pinfunction "B_7") (pintype "passive"))
      (node (ref "R49") (pin "1") (pinfunction "1_1") (pintype "passive"))
      (node (ref "SJ1") (pin "2") (pinfunction "2_2") (pintype "passive"))
    )
    (net (code "5") (name "BAT1") (class "Default")
      (node (ref "Q4") (pin "5") (pinfunction "D_5") (pintype "passive"))
      (node (ref "Q4") (pin "6") (pinfunction "D_6") (pintype "passive"))
      (node (ref "Q4") (pin "7") (pinfunction "D_7") (pintype "passive"))
      (node (ref "Q4") (pin "8") (pinfunction "D_8") (pintype "passive"))
      (node (ref "X2") (pin "2") (pinfunction "KL_2") (pintype "passive"))
    )
    (net (code "6") (name "BAT_POL+") (class "Default")
      (node (ref "Q3") (pin "1") (pinfunction "S_1") (pintype "passive"))
      (node (ref "Q3") (pin "2") (pinfunction "S_2") (pintype "passive"))
      (node (ref "Q3") (pin "3") (pinfunction "S_3") (pintype "passive"))
      (node (ref "Q4") (pin "1") (pinfunction "S_1") (pintype "passive"))
      (node (ref "Q4") (pin "2") (pinfunction "S_2") (pintype "passive"))
      (node (ref "Q4") (pin "3") (pinfunction "S_3") (pintype "passive"))
      (node (ref "R5") (pin "1") (pinfunction "1_1") (pintype "passive"))
    )
    (net (code "7") (name "D+") (class "Default")
      (node (ref "CH2") (pin "5") (pinfunction "D+_5") (pintype "bidirectional"))
      (node (ref "X4") (pin "3") (pinfunction "D+_3") (pintype "bidirectional"))
    )
    (net (code "8") (name "D-") (class "Default")
      (node (ref "CH2") (pin "6") (pinfunction "D-_6") (pintype "bidirectional"))
      (node (ref "X4") (pin "2") (pinfunction "D-_2") (pintype "bidirectional"))
    )
    (net (code "9") (name "DIR_S0") (class "Default")
      (node (ref "S0") (pin "23") (pinfunction "DIR_23") (pintype "bidirectional"))
    )
    (net (code "10") (name "DISAMLE-0") (class "Default")
      (node (ref "U$2") (pin "9") (pinfunction "DISABLE_9") (pintype "bidirectional"))
    )
    (net (code "11") (name "DISAMLE-1") (class "Default")
      (node (ref "U$6") (pin "9") (pinfunction "DISABLE_9") (pintype "bidirectional"))
    )
    (net (code "12") (name "EROR_S0") (class "Default")
      (node (ref "S0") (pin "21") (pinfunction "DIAG_21") (pintype "bidirectional"))
    )
    (net (code "13") (name "GND") (class "Default")
      (node (ref "C1") (pin "2") (pinfunction "2_2") (pintype "passive"))
      (node (ref "C10") (pin "2") (pinfunction "2_2") (pintype "passive"))
      (node (ref "C11") (pin "2") (pinfunction "2_2") (pintype "passive"))
      (node (ref "C14") (pin "2") (pinfunction "2_2") (pintype "passive"))
      (node (ref "C16") (pin "2") (pinfunction "2_2") (pintype "passive"))
      (node (ref "C17") (pin "-") (pinfunction "-_-") (pintype "passive"))
      (node (ref "C18") (pin "2") (pinfunction "2_2") (pintype "passive"))
      (node (ref "C19") (pin "2") (pinfunction "2_2") (pintype "passive"))
      (node (ref "C2") (pin "2") (pinfunction "2_2") (pintype "passive"))
      (node (ref "C20") (pin "-") (pinfunction "-_-") (pintype "passive"))
      (node (ref "C28") (pin "2") (pinfunction "2_2") (pintype "passive"))
      (node (ref "C3") (pin "2") (pinfunction "2_2") (pintype "passive"))
      (node (ref "C30") (pin "2") (pinfunction "2_2") (pintype "passive"))
      (node (ref "C32") (pin "2") (pinfunction "2_2") (pintype "passive"))
      (node (ref "C34") (pin "2") (pinfunction "2_2") (pintype "passive"))
      (node (ref "C35") (pin "2") (pinfunction "2_2") (pintype "passive"))
      (node (ref "C36") (pin "2") (pinfunction "2_2") (pintype "passive"))
      (node (ref "C37") (pin "1") (pinfunction "1_1") (pintype "passive"))
      (node (ref "C38") (pin "-") (pinfunction "-_-") (pintype "passive"))
      (node (ref "C39") (pin "-") (pinfunction "-_-") (pintype "passive"))
      (node (ref "C4") (pin "2") (pinfunction "2_2") (pintype "passive"))
      (node (ref "C5") (pin "2") (pinfunction "2_2") (pintype "passive"))
      (node (ref "C6") (pin "2") (pinfunction "2_2") (pintype "passive"))
      (node (ref "C69") (pin "2") (pinfunction "2_2") (pintype "passive"))
      (node (ref "C7") (pin "2") (pinfunction "2_2") (pintype "passive"))
      (node (ref "C70") (pin "2") (pinfunction "2_2") (pintype "passive"))
      (node (ref "C8") (pin "2") (pinfunction "2_2") (pintype "passive"))
      (node (ref "C9") (pin "2") (pinfunction "2_2") (pintype "passive"))
      (node (ref "CH2") (pin "1") (pinfunction "GND_1") (pintype "bidirectional"))
      (node (ref "IC1") (pin "1") (pinfunction "GND_1") (pintype "input"))
      (node (ref "IC3") (pin "13") (pinfunction "GND_13") (pintype "power_in"))
      (node (ref "IC3") (pin "23") (pinfunction "GND_23") (pintype "power_in"))
      (node (ref "IC3") (pin "3") (pinfunction "AGND_3") (pintype "power_in"))
      (node (ref "IC3") (pin "33") (pinfunction "GND_33") (pintype "power_in"))
      (node (ref "IC3") (pin "43") (pinfunction "GND_43") (pintype "power_in"))
      (node (ref "IC3") (pin "53") (pinfunction "GND_53") (pintype "power_in"))
      (node (ref "IC3") (pin "63") (pinfunction "GND_63") (pintype "power_in"))
      (node (ref "IC3") (pin "73") (pinfunction "GND_73") (pintype "power_in"))
      (node (ref "IC3") (pin "84") (pinfunction "GND_84") (pintype "power_in"))
      (node (ref "IC3") (pin "93") (pinfunction "AGND_93") (pintype "power_in"))
      (node (ref "JP10") (pin "13") (pinfunction "13_13") (pintype "passive"))
      (node (ref "JP10") (pin "23") (pinfunction "23_23") (pintype "passive"))
      (node (ref "JP10") (pin "3") (pinfunction "3_3") (pintype "passive"))
      (node (ref "JP11") (pin "18") (pinfunction "18_18") (pintype "passive"))
      (node (ref "JP11") (pin "8") (pinfunction "8_8") (pintype "passive"))
      (node (ref "JP12") (pin "13") (pinfunction "13_13") (pintype "passive"))
      (node (ref "JP12") (pin "23") (pinfunction "23_23") (pintype "passive"))
      (node (ref "JP12") (pin "3") (pinfunction "3_3") (pintype "passive"))
      (node (ref "JP13") (pin "18") (pinfunction "18_18") (pintype "passive"))
      (node (ref "JP13") (pin "8") (pinfunction "8_8") (pintype "passive"))
      (node (ref "JP14") (pin "13") (pinfunction "13_13") (pintype "passive"))
      (node (ref "JP14") (pin "23") (pinfunction "23_23") (pintype "passive"))
      (node (ref "JP14") (pin "3") (pinfunction "3_3") (pintype "passive"))
      (node (ref "JP15") (pin "18") (pinfunction "18_18") (pintype "passive"))
      (node (ref "JP15") (pin "8") (pinfunction "8_8") (pintype "passive"))
      (node (ref "JP16") (pin "13") (pinfunction "13_13") (pintype "passive"))
      (node (ref "JP16") (pin "23") (pinfunction "23_23") (pintype "passive"))
      (node (ref "JP16") (pin "3") (pinfunction "3_3") (pintype "passive"))
      (node (ref "JP17") (pin "18") (pinfunction "18_18") (pintype "passive"))
      (node (ref "JP17") (pin "8") (pinfunction "8_8") (pintype "passive"))
      (node (ref "JP2") (pin "1") (pinfunction "1_1") (pintype "passive"))
      (node (ref "JP2") (pin "11") (pinfunction "11_11") (pintype "passive"))
      (node (ref "JP2") (pin "13") (pinfunction "13_13") (pintype "passive"))
      (node (ref "JP2") (pin "15") (pinfunction "15_15") (pintype "passive"))
      (node (ref "JP2") (pin "17") (pinfunction "17_17") (pintype "passive"))
      (node (ref "JP2") (pin "19") (pinfunction "19_19") (pintype "passive"))
      (node (ref "JP2") (pin "21") (pinfunction "21_21") (pintype "passive"))
      (node (ref "JP2") (pin "23") (pinfunction "23_23") (pintype "passive"))
      (node (ref "JP2") (pin "25") (pinfunction "25_25") (pintype "passive"))
      (node (ref "JP2") (pin "27") (pinfunction "27_27") (pintype "passive"))
      (node (ref "JP2") (pin "29") (pinfunction "29_29") (pintype "passive"))
      (node (ref "JP2") (pin "3") (pinfunction "3_3") (pintype "passive"))
      (node (ref "JP2") (pin "31") (pinfunction "31_31") (pintype "passive"))
      (node (ref "JP2") (pin "33") (pinfunction "33_33") (pintype "passive"))
      (node (ref "JP2") (pin "35") (pinfunction "35_35") (pintype "passive"))
      (node (ref "JP2") (pin "37") (pinfunction "37_37") (pintype "passive"))
      (node (ref "JP2") (pin "39") (pinfunction "39_39") (pintype "passive"))
      (node (ref "JP2") (pin "41") (pinfunction "41_41") (pintype "passive"))
      (node (ref "JP2") (pin "43") (pinfunction "43_43") (pintype "passive"))
      (node (ref "JP2") (pin "45") (pinfunction "45_45") (pintype "passive"))
      (node (ref "JP2") (pin "47") (pinfunction "47_47") (pintype "passive"))
      (node (ref "JP2") (pin "49") (pinfunction "49_49") (pintype "passive"))
      (node (ref "JP2") (pin "5") (pinfunction "5_5") (pintype "passive"))
      (node (ref "JP2") (pin "7") (pinfunction "7_7") (pintype "passive"))
      (node (ref "JP2") (pin "9") (pinfunction "9_9") (pintype "passive"))
      (node (ref "JP3") (pin "1") (pinfunction "1_1") (pintype "passive"))
      (node (ref "JP3") (pin "11") (pinfunction "11_11") (pintype "passive"))
      (node (ref "JP3") (pin "13") (pinfunction "13_13") (pintype "passive"))
      (node (ref "JP3") (pin "15") (pinfunction "15_15") (pintype "passive"))
      (node (ref "JP3") (pin "17") (pinfunction "17_17") (pintype "passive"))
      (node (ref "JP3") (pin "19") (pinfunction "19_19") (pintype "passive"))
      (node (ref "JP3") (pin "21") (pinfunction "21_21") (pintype "passive"))
      (node (ref "JP3") (pin "23") (pinfunction "23_23") (pintype "passive"))
      (node (ref "JP3") (pin "25") (pinfunction "25_25") (pintype "passive"))
      (node (ref "JP3") (pin "27") (pinfunction "27_27") (pintype "passive"))
      (node (ref "JP3") (pin "29") (pinfunction "29_29") (pintype "passive"))
      (node (ref "JP3") (pin "3") (pinfunction "3_3") (pintype "passive"))
      (node (ref "JP3") (pin "31") (pinfunction "31_31") (pintype "passive"))
      (node (ref "JP3") (pin "33") (pinfunction "33_33") (pintype "passive"))
      (node (ref "JP3") (pin "35") (pinfunction "35_35") (pintype "passive"))
      (node (ref "JP3") (pin "37") (pinfunction "37_37") (pintype "passive"))
      (node (ref "JP3") (pin "39") (pinfunction "39_39") (pintype "passive"))
      (node (ref "JP3") (pin "41") (pinfunction "41_41") (pintype "passive"))
      (node (ref "JP3") (pin "43") (pinfunction "43_43") (pintype "passive"))
      (node (ref "JP3") (pin "45") (pinfunction "45_45") (pintype "passive"))
      (node (ref "JP3") (pin "47") (pinfunction "47_47") (pintype "passive"))
      (node (ref "JP3") (pin "49") (pinfunction "49_49") (pintype "passive"))
      (node (ref "JP3") (pin "5") (pinfunction "5_5") (pintype "passive"))
      (node (ref "JP3") (pin "7") (pinfunction "7_7") (pintype "passive"))
      (node (ref "JP3") (pin "9") (pinfunction "9_9") (pintype "passive"))
      (node (ref "JP4") (pin "1") (pinfunction "1_1") (pintype "passive"))
      (node (ref "JP4") (pin "11") (pinfunction "11_11") (pintype "passive"))
      (node (ref "JP4") (pin "13") (pinfunction "13_13") (pintype "passive"))
      (node (ref "JP4") (pin "15") (pinfunction "15_15") (pintype "passive"))
      (node (ref "JP4") (pin "17") (pinfunction "17_17") (pintype "passive"))
      (node (ref "JP4") (pin "19") (pinfunction "19_19") (pintype "passive"))
      (node (ref "JP4") (pin "21") (pinfunction "21_21") (pintype "passive"))
      (node (ref "JP4") (pin "23") (pinfunction "23_23") (pintype "passive"))
      (node (ref "JP4") (pin "25") (pinfunction "25_25") (pintype "passive"))
      (node (ref "JP4") (pin "27") (pinfunction "27_27") (pintype "passive"))
      (node (ref "JP4") (pin "29") (pinfunction "29_29") (pintype "passive"))
      (node (ref "JP4") (pin "3") (pinfunction "3_3") (pintype "passive"))
      (node (ref "JP4") (pin "31") (pinfunction "31_31") (pintype "passive"))
      (node (ref "JP4") (pin "33") (pinfunction "33_33") (pintype "passive"))
      (node (ref "JP4") (pin "35") (pinfunction "35_35") (pintype "passive"))
      (node (ref "JP4") (pin "37") (pinfunction "37_37") (pintype "passive"))
      (node (ref "JP4") (pin "39") (pinfunction "39_39") (pintype "passive"))
      (node (ref "JP4") (pin "41") (pinfunction "41_41") (pintype "passive"))
      (node (ref "JP4") (pin "43") (pinfunction "43_43") (pintype "passive"))
      (node (ref "JP4") (pin "45") (pinfunction "45_45") (pintype "passive"))
      (node (ref "JP4") (pin "47") (pinfunction "47_47") (pintype "passive"))
      (node (ref "JP4") (pin "49") (pinfunction "49_49") (pintype "passive"))
      (node (ref "JP4") (pin "5") (pinfunction "5_5") (pintype "passive"))
      (node (ref "JP4") (pin "7") (pinfunction "7_7") (pintype "passive"))
      (node (ref "JP4") (pin "9") (pinfunction "9_9") (pintype "passive"))
      (node (ref "JP5") (pin "1") (pinfunction "1_1") (pintype "passive"))
      (node (ref "JP6") (pin "2") (pinfunction "2_2") (pintype "passive"))
      (node (ref "JP7") (pin "2") (pinfunction "2_2") (pintype "passive"))
      (node (ref "JP8") (pin "2") (pinfunction "2_2") (pintype "passive"))
      (node (ref "JP9") (pin "1") (pinfunction "1_1") (pintype "passive"))
      (node (ref "JP9") (pin "11") (pinfunction "11_11") (pintype "passive"))
      (node (ref "JP9") (pin "13") (pinfunction "13_13") (pintype "passive"))
      (node (ref "JP9") (pin "15") (pinfunction "15_15") (pintype "passive"))
      (node (ref "JP9") (pin "17") (pinfunction "17_17") (pintype "passive"))
      (node (ref "JP9") (pin "19") (pinfunction "19_19") (pintype "passive"))
      (node (ref "JP9") (pin "21") (pinfunction "21_21") (pintype "passive"))
      (node (ref "JP9") (pin "23") (pinfunction "23_23") (pintype "passive"))
      (node (ref "JP9") (pin "25") (pinfunction "25_25") (pintype "passive"))
      (node (ref "JP9") (pin "27") (pinfunction "27_27") (pintype "passive"))
      (node (ref "JP9") (pin "29") (pinfunction "29_29") (pintype "passive"))
      (node (ref "JP9") (pin "3") (pinfunction "3_3") (pintype "passive"))
      (node (ref "JP9") (pin "31") (pinfunction "31_31") (pintype "passive"))
      (node (ref "JP9") (pin "33") (pinfunction "33_33") (pintype "passive"))
      (node (ref "JP9") (pin "35") (pinfunction "35_35") (pintype "passive"))
      (node (ref "JP9") (pin "37") (pinfunction "37_37") (pintype "passive"))
      (node (ref "JP9") (pin "39") (pinfunction "39_39") (pintype "passive"))
      (node (ref "JP9") (pin "41") (pinfunction "41_41") (pintype "passive"))
      (node (ref "JP9") (pin "43") (pinfunction "43_43") (pintype "passive"))
      (node (ref "JP9") (pin "45") (pinfunction "45_45") (pintype "passive"))
      (node (ref "JP9") (pin "47") (pinfunction "47_47") (pintype "passive"))
      (node (ref "JP9") (pin "49") (pinfunction "49_49") (pintype "passive"))
      (node (ref "JP9") (pin "5") (pinfunction "5_5") (pintype "passive"))
      (node (ref "JP9") (pin "7") (pinfunction "7_7") (pintype "passive"))
      (node (ref "JP9") (pin "9") (pinfunction "9_9") (pintype "passive"))
      (node (ref "MAX1") (pin "5") (pinfunction "GND_5") (pintype "bidirectional"))
      (node (ref "Q4") (pin "4") (pinfunction "G_4") (pintype "passive"))
      (node (ref "Q7") (pin "2") (pinfunction "S_2") (pintype "passive"))
      (node (ref "R11") (pin "1") (pinfunction "1_1") (pintype "passive"))
      (node (ref "R12") (pin "1") (pinfunction "1_1") (pintype "passive"))
      (node (ref "R14") (pin "1") (pinfunction "1_1") (pintype "passive"))
      (node (ref "R15") (pin "1") (pinfunction "1_1") (pintype "passive"))
      (node (ref "R17") (pin "2") (pinfunction "2_2") (pintype "passive"))
      (node (ref "R50") (pin "2") (pinfunction "2_2") (pintype "passive"))
      (node (ref "R52") (pin "2") (pinfunction "2_2") (pintype "passive"))
      (node (ref "R7") (pin "1") (pinfunction "1_1") (pintype "passive"))
      (node (ref "R9") (pin "1") (pinfunction "1_1") (pintype "passive"))
      (node (ref "S0") (pin "12") (pinfunction "BRB_12") (pintype "bidirectional"))
      (node (ref "S0") (pin "17") (pinfunction "GND_17") (pintype "bidirectional"))
      (node (ref "S0") (pin "24") (pinfunction "ENN_24") (pintype "bidirectional"))
      (node (ref "S0") (pin "27") (pinfunction "CLK_IN_27") (pintype "bidirectional"))
      (node (ref "S0") (pin "3") (pinfunction "GND_3") (pintype "bidirectional"))
      (node (ref "S0") (pin "9") (pinfunction "BRA_9") (pintype "bidirectional"))
      (node (ref "S0") (pin "PAD") (pinfunction "DIE_PAD_PAD") (pintype "bidirectional"))
      (node (ref "SW1") (pin "1") (pinfunction "S_1") (pintype "passive"))
      (node (ref "SW1") (pin "2") (pinfunction "S1_2") (pintype "passive"))
      (node (ref "SW2") (pin "1") (pinfunction "S_1") (pintype "passive"))
      (node (ref "SW2") (pin "2") (pinfunction "S1_2") (pintype "passive"))
      (node (ref "U$1") (pin "4") (pinfunction "GND_4") (pintype "power_in"))
      (node (ref "U$2") (pin "16") (pinfunction "GND_16") (pintype "bidirectional"))
      (node (ref "U$2") (pin "17") (pinfunction "GND_17") (pintype "bidirectional"))
      (node (ref "U$2") (pin "24") (pinfunction "GND_24") (pintype "bidirectional"))
      (node (ref "U$2") (pin "25") (pinfunction "GND_25") (pintype "bidirectional"))
      (node (ref "U$6") (pin "16") (pinfunction "GND_16") (pintype "bidirectional"))
      (node (ref "U$6") (pin "17") (pinfunction "GND_17") (pintype "bidirectional"))
      (node (ref "U$6") (pin "24") (pinfunction "GND_24") (pintype "bidirectional"))
      (node (ref "U$6") (pin "25") (pinfunction "GND_25") (pintype "bidirectional"))
      (node (ref "X2") (pin "1") (pinfunction "KL_1") (pintype "passive"))
      (node (ref "X4") (pin "5") (pinfunction "GND_5") (pintype "passive"))
    )
    (net (code "14") (name "INA-0") (class "Default")
      (node (ref "IC3") (pin "30") (pinfunction "PD5_30") (pintype "bidirectional"))
      (node (ref "JP11") (pin "5") (pinfunction "5_5") (pintype "passive"))
      (node (ref "JP15") (pin "5") (pinfunction "5_5") (pintype "passive"))
      (node (ref "U$2") (pin "7") (pinfunction "IN-A_7") (pintype "bidirectional"))
    )
    (net (code "15") (name "INA-1") (class "Default")
      (node (ref "IC3") (pin "26") (pinfunction "PD1_26") (pintype "bidirectional"))
      (node (ref "JP11") (pin "1") (pinfunction "1_1") (pintype "passive"))
      (node (ref "JP15") (pin "1") (pinfunction "1_1") (pintype "passive"))
      (node (ref "U$6") (pin "7") (pinfunction "IN-A_7") (pintype "bidirectional"))
    )
    (net (code "16") (name "INB-0") (class "Default")
      (node (ref "IC3") (pin "29") (pinfunction "PD4_29") (pintype "bidirectional"))
      (node (ref "JP11") (pin "4") (pinfunction "4_4") (pintype "passive"))
      (node (ref "JP15") (pin "4") (pinfunction "4_4") (pintype "passive"))
      (node (ref "U$2") (pin "8") (pinfunction "IN-B_8") (pintype "bidirectional"))
    )
    (net (code "17") (name "INB-1") (class "Default")
      (node (ref "IC3") (pin "25") (pinfunction "PD0_25") (pintype "bidirectional"))
      (node (ref "JP10") (pin "25") (pinfunction "25_25") (pintype "passive"))
      (node (ref "JP14") (pin "25") (pinfunction "25_25") (pintype "passive"))
      (node (ref "U$6") (pin "8") (pinfunction "IN-B_8") (pintype "bidirectional"))
    )
    (net (code "18") (name "IPROPI-0A") (class "Default")
      (node (ref "IC3") (pin "6") (pinfunction "PB1_6") (pintype "bidirectional"))
      (node (ref "IC3") (pin "96") (pinfunction "PA1_96") (pintype "bidirectional"))
      (node (ref "JP10") (pin "6") (pinfunction "6_6") (pintype "passive"))
      (node (ref "JP13") (pin "21") (pinfunction "21_21") (pintype "passive"))
      (node (ref "JP14") (pin "6") (pinfunction "6_6") (pintype "passive"))
      (node (ref "JP17") (pin "21") (pinfunction "21_21") (pintype "passive"))
      (node (ref "R12") (pin "2") (pinfunction "2_2") (pintype "passive"))
      (node (ref "U$2") (pin "10") (pinfunction "IPROPI-A_10") (pintype "bidirectional"))
    )
    (net (code "19") (name "IPROPI-0B") (class "Default")
      (node (ref "IC3") (pin "5") (pinfunction "PB0_5") (pintype "bidirectional"))
      (node (ref "IC3") (pin "95") (pinfunction "PA0_95") (pintype "bidirectional"))
      (node (ref "JP10") (pin "5") (pinfunction "5_5") (pintype "passive"))
      (node (ref "JP13") (pin "20") (pinfunction "20_20") (pintype "passive"))
      (node (ref "JP14") (pin "5") (pinfunction "5_5") (pintype "passive"))
      (node (ref "JP17") (pin "20") (pinfunction "20_20") (pintype "passive"))
      (node (ref "R11") (pin "2") (pinfunction "2_2") (pintype "passive"))
      (node (ref "U$2") (pin "12") (pinfunction "IPROPI-B_12") (pintype "bidirectional"))
    )
    (net (code "20") (name "IPROPI-1A") (class "Default")
      (node (ref "R15") (pin "2") (pinfunction "2_2") (pintype "passive"))
      (node (ref "U$6") (pin "10") (pinfunction "IPROPI-A_10") (pintype "bidirectional"))
    )
    (net (code "21") (name "IPROPI-1B") (class "Default")
      (node (ref "R14") (pin "2") (pinfunction "2_2") (pintype "passive"))
      (node (ref "U$6") (pin "12") (pinfunction "IPROPI-B_12") (pintype "bidirectional"))
    )
    (net (code "22") (name "LED0") (class "Default")
      (node (ref "IC3") (pin "55") (pinfunction "PH0_55") (pintype "bidirectional"))
    )
    (net (code "23") (name "LED1") (class "Default")
      (node (ref "IC3") (pin "56") (pinfunction "PH1_56") (pintype "bidirectional"))
    )
    (net (code "24") (name "LED2") (class "Default")
      (node (ref "IC3") (pin "57") (pinfunction "PH2_57") (pintype "bidirectional"))
    )
    (net (code "25") (name "LED3") (class "Default")
      (node (ref "IC3") (pin "58") (pinfunction "PH3_58") (pintype "bidirectional"))
    )
    (net (code "26") (name "MISO") (class "Default")
      (node (ref "IC3") (pin "21") (pinfunction "PC6_21") (pintype "bidirectional"))
      (node (ref "JP10") (pin "21") (pinfunction "21_21") (pintype "passive"))
      (node (ref "JP14") (pin "21") (pinfunction "21_21") (pintype "passive"))
      (node (ref "U$2") (pin "3") (pinfunction "SDO_3") (pintype "bidirectional"))
      (node (ref "U$6") (pin "3") (pinfunction "SDO_3") (pintype "bidirectional"))
    )
    (net (code "27") (name "MODE_485") (class "Default")
      (node (ref "IC3") (pin "40") (pinfunction "PE5_40") (pintype "bidirectional"))
      (node (ref "MAX1") (pin "2") (pinfunction "RE/_2") (pintype "input"))
      (node (ref "MAX1") (pin "3") (pinfunction "DE_3") (pintype "input"))
      (node (ref "R52") (pin "1") (pinfunction "1_1") (pintype "passive"))
    )
    (net (code "28") (name "MOSI") (class "Default")
      (node (ref "IC3") (pin "20") (pinfunction "PC5_20") (pintype "bidirectional"))
      (node (ref "JP10") (pin "20") (pinfunction "20_20") (pintype "passive"))
      (node (ref "JP14") (pin "20") (pinfunction "20_20") (pintype "passive"))
      (node (ref "U$2") (pin "4") (pinfunction "SDI_4") (pintype "bidirectional"))
      (node (ref "U$6") (pin "4") (pinfunction "SDI_4") (pintype "bidirectional"))
    )
    (net (code "29") (name "NFAUL-0") (class "Default")
      (node (ref "IC3") (pin "32") (pinfunction "PD7_32") (pintype "bidirectional"))
      (node (ref "JP11") (pin "7") (pinfunction "7_7") (pintype "passive"))
      (node (ref "JP15") (pin "7") (pinfunction "7_7") (pintype "passive"))
      (node (ref "R13") (pin "1") (pinfunction "1_1") (pintype "passive"))
      (node (ref "U$2") (pin "2") (pinfunction "FAOU_2") (pintype "bidirectional"))
    )
    (net (code "30") (name "NFAUL-1") (class "Default")
      (node (ref "IC3") (pin "28") (pinfunction "PD3_28") (pintype "bidirectional"))
      (node (ref "JP11") (pin "3") (pinfunction "3_3") (pintype "passive"))
      (node (ref "JP15") (pin "3") (pinfunction "3_3") (pintype "passive"))
      (node (ref "R16") (pin "1") (pinfunction "1_1") (pintype "passive"))
      (node (ref "U$6") (pin "2") (pinfunction "FAOU_2") (pintype "bidirectional"))
    )
    (net (code "31") (name "NSLEEP-0") (class "Default")
      (node (ref "IC3") (pin "31") (pinfunction "PD6_31") (pintype "bidirectional"))
      (node (ref "JP11") (pin "6") (pinfunction "6_6") (pintype "passive"))
      (node (ref "JP15") (pin "6") (pinfunction "6_6") (pintype "passive"))
      (node (ref "U$2") (pin "11") (pinfunction "NSLEEP_11") (pintype "bidirectional"))
    )
    (net (code "32") (name "NSLEEP-1") (class "Default")
      (node (ref "IC3") (pin "27") (pinfunction "PD2_27") (pintype "bidirectional"))
      (node (ref "JP11") (pin "2") (pinfunction "2_2") (pintype "passive"))
      (node (ref "JP15") (pin "2") (pinfunction "2_2") (pintype "passive"))
      (node (ref "U$6") (pin "11") (pinfunction "NSLEEP_11") (pintype "bidirectional"))
    )
    (net (code "33") (name "Net-(JP1-Pad2)") (class "Default")
      (node (ref "JP1") (pin "2") (pinfunction "2_2") (pintype "passive"))
      (node (ref "R1") (pin "1") (pinfunction "1_1") (pintype "passive"))
    )
    (net (code "34") (name "Net-(MAX1-RO)") (class "Default")
      (node (ref "MAX1") (pin "1") (pinfunction "RO_1") (pintype "output"))
      (node (ref "Q10") (pin "3") (pinfunction "D_3") (pintype "passive"))
    )
    (net (code "35") (name "Net-(Q8-D)") (class "Default")
      (node (ref "Q8") (pin "3") (pinfunction "D_3") (pintype "passive"))
      (node (ref "R8") (pin "2") (pinfunction "2_2") (pintype "passive"))
      (node (ref "U$1") (pin "1") (pinfunction "SWC_1") (pintype "input"))
      (node (ref "U$1") (pin "7") (pinfunction "IPK_7") (pintype "bidirectional"))
      (node (ref "U$1") (pin "8") (pinfunction "DC_8") (pintype "input"))
    )
    (net (code "36") (name "Net-(Q8-G)") (class "Default")
      (node (ref "Q8") (pin "1") (pinfunction "G_1") (pintype "passive"))
      (node (ref "R7") (pin "2") (pinfunction "2_2") (pintype "passive"))
      (node (ref "U$1") (pin "2") (pinfunction "SWE_2") (pintype "input"))
    )
    (net (code "37") (name "Net-(Q8-S)") (class "Default")
      (node (ref "L2") (pin "1") (pinfunction "1_1") (pintype "passive"))
      (node (ref "Q8") (pin "2") (pinfunction "S_2") (pintype "passive"))
    )
    (net (code "38") (name "Net-(R48-Pad1)") (class "Default")
      (node (ref "R48") (pin "1") (pinfunction "1_1") (pintype "passive"))
      (node (ref "SJ1") (pin "1") (pinfunction "1_1") (pintype "passive"))
    )
    (net (code "39") (name "Net-(S0-5VOUT)") (class "Default")
      (node (ref "C18") (pin "1") (pinfunction "1_1") (pintype "passive"))
      (node (ref "S0") (pin "18") (pinfunction "5VOUT_18") (pintype "bidirectional"))
    )
    (net (code "40") (name "Net-(S0-CPI)") (class "Default")
      (node (ref "C15") (pin "2") (pinfunction "2_2") (pintype "passive"))
      (node (ref "S0") (pin "5") (pinfunction "CPI_5") (pintype "bidirectional"))
    )
    (net (code "41") (name "Net-(S0-CPO)") (class "Default")
      (node (ref "C15") (pin "1") (pinfunction "1_1") (pintype "passive"))
      (node (ref "S0") (pin "4") (pinfunction "CPO_4") (pintype "bidirectional"))
    )
    (net (code "42") (name "Net-(S0-OA1)") (class "Default")
      (node (ref "S0") (pin "10") (pinfunction "OA1_10") (pintype "bidirectional"))
      (node (ref "X1") (pin "1") (pinfunction "KL_1") (pintype "passive"))
    )
    (net (code "43") (name "Net-(S0-OA2)") (class "Default")
      (node (ref "S0") (pin "8") (pinfunction "OA2_8") (pintype "bidirectional"))
      (node (ref "X1") (pin "2") (pinfunction "KL_2") (pintype "passive"))
    )
    (net (code "44") (name "Net-(S0-OB1)") (class "Default")
      (node (ref "S0") (pin "11") (pinfunction "OB1_11") (pintype "bidirectional"))
      (node (ref "X3") (pin "1") (pinfunction "KL_1") (pintype "passive"))
    )
    (net (code "45") (name "Net-(S0-OB2)") (class "Default")
      (node (ref "S0") (pin "13") (pinfunction "OB2_13") (pintype "bidirectional"))
      (node (ref "X3") (pin "2") (pinfunction "KL_2") (pintype "passive"))
    )
    (net (code "46") (name "Net-(S0-VCP)") (class "Default")
      (node (ref "C13") (pin "2") (pinfunction "2_2") (pintype "passive"))
      (node (ref "S0") (pin "6") (pinfunction "VCP_6") (pintype "bidirectional"))
    )
    (net (code "47") (name "Net-(U$1-COMP)") (class "Default")
      (node (ref "R10") (pin "2") (pinfunction "2_2") (pintype "passive"))
      (node (ref "R9") (pin "2") (pinfunction "2_2") (pintype "passive"))
      (node (ref "U$1") (pin "5") (pinfunction "COMP_5") (pintype "input"))
    )
    (net (code "48") (name "Net-(U$1-TC)") (class "Default")
      (node (ref "C11") (pin "1") (pinfunction "1_1") (pintype "passive"))
      (node (ref "U$1") (pin "3") (pinfunction "TC_3") (pintype "input"))
    )
    (net (code "49") (name "Net-(U$2-CPH)") (class "Default")
      (node (ref "C27") (pin "1") (pinfunction "1_1") (pintype "passive"))
      (node (ref "U$2") (pin "22") (pinfunction "CPH_22") (pintype "bidirectional"))
    )
    (net (code "50") (name "Net-(U$2-CPL)") (class "Default")
      (node (ref "C27") (pin "2") (pinfunction "2_2") (pintype "passive"))
      (node (ref "U$2") (pin "23") (pinfunction "CPL_23") (pintype "bidirectional"))
    )
    (net (code "51") (name "Net-(U$2-VCP)") (class "Default")
      (node (ref "C29") (pin "2") (pinfunction "2_2") (pintype "passive"))
      (node (ref "U$2") (pin "21") (pinfunction "VCP_21") (pintype "bidirectional"))
    )
    (net (code "52") (name "Net-(U$6-CPH)") (class "Default")
      (node (ref "C31") (pin "1") (pinfunction "1_1") (pintype "passive"))
      (node (ref "U$6") (pin "22") (pinfunction "CPH_22") (pintype "bidirectional"))
    )
    (net (code "53") (name "Net-(U$6-CPL)") (class "Default")
      (node (ref "C31") (pin "2") (pinfunction "2_2") (pintype "passive"))
      (node (ref "U$6") (pin "23") (pinfunction "CPL_23") (pintype "bidirectional"))
    )
    (net (code "54") (name "Net-(U$6-VCP)") (class "Default")
      (node (ref "C33") (pin "2") (pinfunction "2_2") (pintype "passive"))
      (node (ref "U$6") (pin "21") (pinfunction "VCP_21") (pintype "bidirectional"))
    )
    (net (code "55") (name "Net-(X5A-KL)") (class "Default")
      (node (ref "U$2") (pin "14") (pinfunction "OUT-B_14") (pintype "bidirectional"))
      (node (ref "U$2") (pin "15") (pinfunction "OUT-B_15") (pintype "bidirectional"))
      (node (ref "X5") (pin "1") (pinfunction "KL_1") (pintype "passive"))
    )
    (net (code "56") (name "Net-(X5B-KL)") (class "Default")
      (node (ref "U$2") (pin "18") (pinfunction "OUT-A_18") (pintype "bidirectional"))
      (node (ref "U$2") (pin "19") (pinfunction "OUT-A_19") (pintype "bidirectional"))
      (node (ref "X5") (pin "2") (pinfunction "KL_2") (pintype "passive"))
    )
    (net (code "57") (name "Net-(X6A-KL)") (class "Default")
      (node (ref "U$6") (pin "14") (pinfunction "OUT-B_14") (pintype "bidirectional"))
      (node (ref "U$6") (pin "15") (pinfunction "OUT-B_15") (pintype "bidirectional"))
      (node (ref "X6") (pin "1") (pinfunction "KL_1") (pintype "passive"))
    )
    (net (code "58") (name "Net-(X6B-KL)") (class "Default")
      (node (ref "U$6") (pin "18") (pinfunction "OUT-A_18") (pintype "bidirectional"))
      (node (ref "U$6") (pin "19") (pinfunction "OUT-A_19") (pintype "bidirectional"))
      (node (ref "X6") (pin "2") (pinfunction "KL_2") (pintype "passive"))
    )
    (net (code "59") (name "OFF") (class "Default")
      (node (ref "C37") (pin "2") (pinfunction "2_2") (pintype "passive"))
      (node (ref "IC3") (pin "72") (pinfunction "PJ7_72") (pintype "bidirectional"))
      (node (ref "JP1") (pin "3") (pinfunction "3_3") (pintype "passive"))
      (node (ref "JP8") (pin "1") (pinfunction "1_1") (pintype "passive"))
      (node (ref "Q7") (pin "1") (pinfunction "G_1") (pintype "passive"))
      (node (ref "R1") (pin "2") (pinfunction "2_2") (pintype "passive"))
      (node (ref "R17") (pin "1") (pinfunction "1_1") (pintype "passive"))
      (node (ref "SW2") (pin "3") (pinfunction "P_3") (pintype "passive"))
      (node (ref "SW2") (pin "4") (pinfunction "P1_4") (pintype "passive"))
    )
    (net (code "60") (name "ON") (class "Default")
      (node (ref "C12") (pin "2") (pinfunction "2_2") (pintype "passive"))
      (node (ref "JP7") (pin "1") (pinfunction "1_1") (pintype "passive"))
      (node (ref "R6") (pin "2") (pinfunction "2_2") (pintype "passive"))
      (node (ref "SW1") (pin "3") (pinfunction "P_3") (pintype "passive"))
      (node (ref "SW1") (pin "4") (pinfunction "P1_4") (pintype "passive"))
    )
    (net (code "61") (name "PA2") (class "Default")
      (node (ref "IC3") (pin "97") (pinfunction "PA2_97") (pintype "bidirectional"))
      (node (ref "JP13") (pin "22") (pinfunction "22_22") (pintype "passive"))
      (node (ref "JP17") (pin "22") (pinfunction "22_22") (pintype "passive"))
    )
    (net (code "62") (name "PA3") (class "Default")
      (node (ref "IC3") (pin "98") (pinfunction "PA3_98") (pintype "bidirectional"))
      (node (ref "JP13") (pin "23") (pinfunction "23_23") (pintype "passive"))
      (node (ref "JP17") (pin "23") (pinfunction "23_23") (pintype "passive"))
    )
    (net (code "63") (name "PA4") (class "Default")
      (node (ref "IC3") (pin "99") (pinfunction "PA4_99") (pintype "bidirectional"))
      (node (ref "JP13") (pin "24") (pinfunction "24_24") (pintype "passive"))
      (node (ref "JP17") (pin "24") (pinfunction "24_24") (pintype "passive"))
    )
    (net (code "64") (name "PA5") (class "Default")
      (node (ref "IC3") (pin "100") (pinfunction "PA5_100") (pintype "bidirectional"))
      (node (ref "JP13") (pin "25") (pinfunction "25_25") (pintype "passive"))
      (node (ref "JP17") (pin "25") (pinfunction "25_25") (pintype "passive"))
    )
    (net (code "65") (name "PA6") (class "Default")
      (node (ref "IC3") (pin "1") (pinfunction "PA6_1") (pintype "bidirectional"))
      (node (ref "JP10") (pin "1") (pinfunction "1_1") (pintype "passive"))
      (node (ref "JP14") (pin "1") (pinfunction "1_1") (pintype "passive"))
    )
    (net (code "66") (name "PA7") (class "Default")
      (node (ref "IC3") (pin "2") (pinfunction "PA7_2") (pintype "bidirectional"))
      (node (ref "JP10") (pin "2") (pinfunction "2_2") (pintype "passive"))
      (node (ref "JP14") (pin "2") (pinfunction "2_2") (pintype "passive"))
    )
    (net (code "67") (name "PB2") (class "Default")
      (node (ref "IC3") (pin "7") (pinfunction "PB2_7") (pintype "bidirectional"))
      (node (ref "JP10") (pin "7") (pinfunction "7_7") (pintype "passive"))
      (node (ref "JP14") (pin "7") (pinfunction "7_7") (pintype "passive"))
    )
    (net (code "68") (name "PB3") (class "Default")
      (node (ref "IC3") (pin "8") (pinfunction "PB3_8") (pintype "bidirectional"))
      (node (ref "JP10") (pin "8") (pinfunction "8_8") (pintype "passive"))
      (node (ref "JP14") (pin "8") (pinfunction "8_8") (pintype "passive"))
    )
    (net (code "69") (name "PB4") (class "Default")
      (node (ref "IC3") (pin "9") (pinfunction "PB4_9") (pintype "bidirectional"))
      (node (ref "JP10") (pin "9") (pinfunction "9_9") (pintype "passive"))
      (node (ref "JP14") (pin "9") (pinfunction "9_9") (pintype "passive"))
    )
    (net (code "70") (name "PB5") (class "Default")
      (node (ref "IC3") (pin "10") (pinfunction "PB5_10") (pintype "bidirectional"))
      (node (ref "JP10") (pin "10") (pinfunction "10_10") (pintype "passive"))
      (node (ref "JP14") (pin "10") (pinfunction "10_10") (pintype "passive"))
    )
    (net (code "71") (name "PB6") (class "Default")
      (node (ref "IC3") (pin "11") (pinfunction "PB6_11") (pintype "bidirectional"))
      (node (ref "JP10") (pin "11") (pinfunction "11_11") (pintype "passive"))
      (node (ref "JP14") (pin "11") (pinfunction "11_11") (pintype "passive"))
    )
    (net (code "72") (name "PB7") (class "Default")
      (node (ref "IC3") (pin "12") (pinfunction "PB7_12") (pintype "bidirectional"))
      (node (ref "JP10") (pin "12") (pinfunction "12_12") (pintype "passive"))
      (node (ref "JP14") (pin "12") (pinfunction "12_12") (pintype "passive"))
    )
    (net (code "73") (name "PC0") (class "Default")
      (node (ref "IC3") (pin "15") (pinfunction "PC0_15") (pintype "bidirectional"))
      (node (ref "JP10") (pin "15") (pinfunction "15_15") (pintype "passive"))
      (node (ref "JP14") (pin "15") (pinfunction "15_15") (pintype "passive"))
    )
    (net (code "74") (name "PC1") (class "Default")
      (node (ref "IC3") (pin "16") (pinfunction "PC1_16") (pintype "bidirectional"))
      (node (ref "JP10") (pin "16") (pinfunction "16_16") (pintype "passive"))
      (node (ref "JP14") (pin "16") (pinfunction "16_16") (pintype "passive"))
    )
    (net (code "75") (name "PC2") (class "Default")
      (node (ref "IC3") (pin "17") (pinfunction "PC2_17") (pintype "bidirectional"))
      (node (ref "JP10") (pin "17") (pinfunction "17_17") (pintype "passive"))
      (node (ref "JP14") (pin "17") (pinfunction "17_17") (pintype "passive"))
    )
    (net (code "76") (name "PDI_DATA") (class "Default")
      (node (ref "IC3") (pin "89") (pinfunction "PDI_DATA_89") (pintype "bidirectional"))
      (node (ref "JP13") (pin "14") (pinfunction "14_14") (pintype "passive"))
      (node (ref "JP17") (pin "14") (pinfunction "14_14") (pintype "passive"))
      (node (ref "JP6") (pin "4") (pinfunction "4_4") (pintype "passive"))
    )
    (net (code "77") (name "PDN{slash}UART") (class "Default")
      (node (ref "S0") (pin "20") (pinfunction "PDN/UART_20") (pintype "bidirectional"))
    )
    (net (code "78") (name "PE0") (class "Default")
      (node (ref "IC3") (pin "35") (pinfunction "PE0_35") (pintype "bidirectional"))
      (node (ref "JP11") (pin "10") (pinfunction "10_10") (pintype "passive"))
      (node (ref "JP15") (pin "10") (pinfunction "10_10") (pintype "passive"))
    )
    (net (code "79") (name "PE1") (class "Default")
      (node (ref "IC3") (pin "36") (pinfunction "PE1_36") (pintype "bidirectional"))
      (node (ref "JP11") (pin "11") (pinfunction "11_11") (pintype "passive"))
      (node (ref "JP15") (pin "11") (pinfunction "11_11") (pintype "passive"))
    )
    (net (code "80") (name "PE2") (class "Default")
      (node (ref "IC3") (pin "37") (pinfunction "PE2_37") (pintype "bidirectional"))
      (node (ref "JP11") (pin "12") (pinfunction "12_12") (pintype "passive"))
      (node (ref "JP15") (pin "12") (pinfunction "12_12") (pintype "passive"))
    )
    (net (code "81") (name "PE3") (class "Default")
      (node (ref "IC3") (pin "38") (pinfunction "PE3_38") (pintype "bidirectional"))
      (node (ref "JP11") (pin "13") (pinfunction "13_13") (pintype "passive"))
      (node (ref "JP15") (pin "13") (pinfunction "13_13") (pintype "passive"))
    )
    (net (code "82") (name "PE4") (class "Default")
      (node (ref "IC3") (pin "39") (pinfunction "PE4_39") (pintype "bidirectional"))
      (node (ref "JP11") (pin "14") (pinfunction "14_14") (pintype "passive"))
      (node (ref "JP15") (pin "14") (pinfunction "14_14") (pintype "passive"))
    )
    (net (code "83") (name "PE5") (class "Default")
      (node (ref "JP11") (pin "15") (pinfunction "15_15") (pintype "passive"))
      (node (ref "JP15") (pin "15") (pinfunction "15_15") (pintype "passive"))
    )
    (net (code "84") (name "PF0") (class "Default")
      (node (ref "IC3") (pin "45") (pinfunction "PF0_45") (pintype "bidirectional"))
      (node (ref "JP11") (pin "20") (pinfunction "20_20") (pintype "passive"))
      (node (ref "JP15") (pin "20") (pinfunction "20_20") (pintype "passive"))
    )
    (net (code "85") (name "PF1") (class "Default")
      (node (ref "IC3") (pin "46") (pinfunction "PF1_46") (pintype "bidirectional"))
      (node (ref "JP11") (pin "21") (pinfunction "21_21") (pintype "passive"))
      (node (ref "JP15") (pin "21") (pinfunction "21_21") (pintype "passive"))
    )
    (net (code "86") (name "PF2") (class "Default")
      (node (ref "IC3") (pin "47") (pinfunction "PF2_47") (pintype "bidirectional"))
      (node (ref "JP11") (pin "22") (pinfunction "22_22") (pintype "passive"))
      (node (ref "JP15") (pin "22") (pinfunction "22_22") (pintype "passive"))
    )
    (net (code "87") (name "PF3") (class "Default")
      (node (ref "IC3") (pin "48") (pinfunction "PF3_48") (pintype "bidirectional"))
      (node (ref "JP11") (pin "23") (pinfunction "23_23") (pintype "passive"))
      (node (ref "JP15") (pin "23") (pinfunction "23_23") (pintype "passive"))
    )
    (net (code "88") (name "PF4") (class "Default")
      (node (ref "IC3") (pin "49") (pinfunction "PF4_49") (pintype "bidirectional"))
      (node (ref "JP11") (pin "24") (pinfunction "24_24") (pintype "passive"))
      (node (ref "JP15") (pin "24") (pinfunction "24_24") (pintype "passive"))
    )
    (net (code "89") (name "PF5") (class "Default")
      (node (ref "IC3") (pin "50") (pinfunction "PF5_50") (pintype "bidirectional"))
      (node (ref "JP11") (pin "25") (pinfunction "25_25") (pintype "passive"))
      (node (ref "JP15") (pin "25") (pinfunction "25_25") (pintype "passive"))
    )
    (net (code "90") (name "PH0") (class "Default")
      (node (ref "JP12") (pin "5") (pinfunction "5_5") (pintype "passive"))
      (node (ref "JP16") (pin "5") (pinfunction "5_5") (pintype "passive"))
    )
    (net (code "91") (name "PH1") (class "Default")
      (node (ref "JP12") (pin "6") (pinfunction "6_6") (pintype "passive"))
      (node (ref "JP16") (pin "6") (pinfunction "6_6") (pintype "passive"))
    )
    (net (code "92") (name "PH2") (class "Default")
      (node (ref "JP12") (pin "7") (pinfunction "7_7") (pintype "passive"))
      (node (ref "JP16") (pin "7") (pinfunction "7_7") (pintype "passive"))
    )
    (net (code "93") (name "PH3") (class "Default")
      (node (ref "JP12") (pin "8") (pinfunction "8_8") (pintype "passive"))
      (node (ref "JP16") (pin "8") (pinfunction "8_8") (pintype "passive"))
    )
    (net (code "94") (name "PH4") (class "Default")
      (node (ref "JP12") (pin "9") (pinfunction "9_9") (pintype "passive"))
      (node (ref "JP16") (pin "9") (pinfunction "9_9") (pintype "passive"))
    )
    (net (code "95") (name "PH5") (class "Default")
      (node (ref "JP12") (pin "10") (pinfunction "10_10") (pintype "passive"))
      (node (ref "JP16") (pin "10") (pinfunction "10_10") (pintype "passive"))
    )
    (net (code "96") (name "PH6") (class "Default")
      (node (ref "JP12") (pin "11") (pinfunction "11_11") (pintype "passive"))
      (node (ref "JP16") (pin "11") (pinfunction "11_11") (pintype "passive"))
    )
    (net (code "97") (name "PH7") (class "Default")
      (node (ref "JP12") (pin "12") (pinfunction "12_12") (pintype "passive"))
      (node (ref "JP16") (pin "12") (pinfunction "12_12") (pintype "passive"))
    )
    (net (code "98") (name "PJ0") (class "Default")
      (node (ref "IC3") (pin "65") (pinfunction "PJ0_65") (pintype "bidirectional"))
      (node (ref "JP12") (pin "15") (pinfunction "15_15") (pintype "passive"))
      (node (ref "JP16") (pin "15") (pinfunction "15_15") (pintype "passive"))
    )
    (net (code "99") (name "PJ1") (class "Default")
      (node (ref "IC3") (pin "66") (pinfunction "PJ1_66") (pintype "bidirectional"))
      (node (ref "JP12") (pin "16") (pinfunction "16_16") (pintype "passive"))
      (node (ref "JP16") (pin "16") (pinfunction "16_16") (pintype "passive"))
    )
    (net (code "100") (name "PJ2") (class "Default")
      (node (ref "IC3") (pin "67") (pinfunction "PJ2_67") (pintype "bidirectional"))
      (node (ref "JP12") (pin "17") (pinfunction "17_17") (pintype "passive"))
      (node (ref "JP16") (pin "17") (pinfunction "17_17") (pintype "passive"))
    )
    (net (code "101") (name "PJ3") (class "Default")
      (node (ref "IC3") (pin "68") (pinfunction "PJ3_68") (pintype "bidirectional"))
      (node (ref "JP12") (pin "18") (pinfunction "18_18") (pintype "passive"))
      (node (ref "JP16") (pin "18") (pinfunction "18_18") (pintype "passive"))
    )
    (net (code "102") (name "PJ4") (class "Default")
      (node (ref "IC3") (pin "69") (pinfunction "PJ4_69") (pintype "bidirectional"))
      (node (ref "JP12") (pin "19") (pinfunction "19_19") (pintype "passive"))
      (node (ref "JP16") (pin "19") (pinfunction "19_19") (pintype "passive"))
    )
    (net (code "103") (name "PJ5") (class "Default")
      (node (ref "IC3") (pin "70") (pinfunction "PJ5_70") (pintype "bidirectional"))
      (node (ref "JP12") (pin "20") (pinfunction "20_20") (pintype "passive"))
      (node (ref "JP16") (pin "20") (pinfunction "20_20") (pintype "passive"))
    )
    (net (code "104") (name "PJ6") (class "Default")
      (node (ref "IC3") (pin "71") (pinfunction "PJ6_71") (pintype "bidirectional"))
      (node (ref "JP12") (pin "21") (pinfunction "21_21") (pintype "passive"))
      (node (ref "JP16") (pin "21") (pinfunction "21_21") (pintype "passive"))
    )
    (net (code "105") (name "PJ7") (class "Default")
      (node (ref "JP12") (pin "22") (pinfunction "22_22") (pintype "passive"))
      (node (ref "JP16") (pin "22") (pinfunction "22_22") (pintype "passive"))
    )
    (net (code "106") (name "PK0") (class "Default")
      (node (ref "IC3") (pin "75") (pinfunction "PK0_75") (pintype "bidirectional"))
      (node (ref "JP12") (pin "25") (pinfunction "25_25") (pintype "passive"))
      (node (ref "JP16") (pin "25") (pinfunction "25_25") (pintype "passive"))
    )
    (net (code "107") (name "PK1") (class "Default")
      (node (ref "IC3") (pin "76") (pinfunction "PK1_76") (pintype "bidirectional"))
      (node (ref "JP13") (pin "1") (pinfunction "1_1") (pintype "passive"))
      (node (ref "JP17") (pin "1") (pinfunction "1_1") (pintype "passive"))
    )
    (net (code "108") (name "PK2") (class "Default")
      (node (ref "IC3") (pin "77") (pinfunction "PK2_77") (pintype "bidirectional"))
      (node (ref "JP13") (pin "2") (pinfunction "2_2") (pintype "passive"))
      (node (ref "JP17") (pin "2") (pinfunction "2_2") (pintype "passive"))
    )
    (net (code "109") (name "PK3") (class "Default")
      (node (ref "IC3") (pin "78") (pinfunction "PK3_78") (pintype "bidirectional"))
      (node (ref "JP13") (pin "3") (pinfunction "3_3") (pintype "passive"))
      (node (ref "JP17") (pin "3") (pinfunction "3_3") (pintype "passive"))
    )
    (net (code "110") (name "PK4") (class "Default")
      (node (ref "IC3") (pin "79") (pinfunction "PK4_79") (pintype "bidirectional"))
      (node (ref "JP13") (pin "4") (pinfunction "4_4") (pintype "passive"))
      (node (ref "JP17") (pin "4") (pinfunction "4_4") (pintype "passive"))
    )
    (net (code "111") (name "PK5") (class "Default")
      (node (ref "IC3") (pin "80") (pinfunction "PK5_80") (pintype "bidirectional"))
      (node (ref "JP13") (pin "5") (pinfunction "5_5") (pintype "passive"))
      (node (ref "JP17") (pin "5") (pinfunction "5_5") (pintype "passive"))
    )
    (net (code "112") (name "PK6") (class "Default")
      (node (ref "IC3") (pin "81") (pinfunction "PK6_81") (pintype "bidirectional"))
      (node (ref "JP13") (pin "6") (pinfunction "6_6") (pintype "passive"))
      (node (ref "JP17") (pin "6") (pinfunction "6_6") (pintype "passive"))
    )
    (net (code "113") (name "PK7") (class "Default")
      (node (ref "IC3") (pin "82") (pinfunction "PK7_82") (pintype "bidirectional"))
      (node (ref "JP13") (pin "7") (pinfunction "7_7") (pintype "passive"))
      (node (ref "JP17") (pin "7") (pinfunction "7_7") (pintype "passive"))
    )
    (net (code "114") (name "PQ0") (class "Default")
      (node (ref "IC3") (pin "85") (pinfunction "PQ0_85") (pintype "bidirectional"))
      (node (ref "JP13") (pin "10") (pinfunction "10_10") (pintype "passive"))
      (node (ref "JP17") (pin "10") (pinfunction "10_10") (pintype "passive"))
    )
    (net (code "115") (name "PQ1") (class "Default")
      (node (ref "IC3") (pin "86") (pinfunction "PQ1_86") (pintype "bidirectional"))
      (node (ref "JP13") (pin "11") (pinfunction "11_11") (pintype "passive"))
      (node (ref "JP17") (pin "11") (pinfunction "11_11") (pintype "passive"))
    )
    (net (code "116") (name "PQ2") (class "Default")
      (node (ref "IC3") (pin "87") (pinfunction "PQ2_87") (pintype "bidirectional"))
      (node (ref "JP13") (pin "12") (pinfunction "12_12") (pintype "passive"))
      (node (ref "JP17") (pin "12") (pinfunction "12_12") (pintype "passive"))
    )
    (net (code "117") (name "PQ3") (class "Default")
      (node (ref "IC3") (pin "88") (pinfunction "PQ3_88") (pintype "bidirectional"))
      (node (ref "JP13") (pin "13") (pinfunction "13_13") (pintype "passive"))
      (node (ref "JP17") (pin "13") (pinfunction "13_13") (pintype "passive"))
    )
    (net (code "118") (name "PR0") (class "Default")
      (node (ref "IC3") (pin "91") (pinfunction "PR0_91") (pintype "bidirectional"))
      (node (ref "JP13") (pin "16") (pinfunction "16_16") (pintype "passive"))
      (node (ref "JP17") (pin "16") (pinfunction "16_16") (pintype "passive"))
    )
    (net (code "119") (name "PR1") (class "Default")
      (node (ref "IC3") (pin "92") (pinfunction "PR1_92") (pintype "bidirectional"))
      (node (ref "JP13") (pin "17") (pinfunction "17_17") (pintype "passive"))
      (node (ref "JP17") (pin "17") (pinfunction "17_17") (pintype "passive"))
    )
    (net (code "120") (name "RESET") (class "Default")
      (node (ref "JP6") (pin "3") (pinfunction "3_3") (pintype "passive"))
    )
    (net (code "121") (name "RX") (class "Default")
      (node (ref "IC3") (pin "51") (pinfunction "PF6_51") (pintype "bidirectional"))
      (node (ref "JP12") (pin "1") (pinfunction "1_1") (pintype "passive"))
      (node (ref "JP16") (pin "1") (pinfunction "1_1") (pintype "passive"))
    )
    (net (code "122") (name "RXD0") (class "Default")
      (node (ref "CH2") (pin "2") (pinfunction "TX_2") (pintype "bidirectional"))
    )
    (net (code "123") (name "RX_485") (class "Default")
      (node (ref "IC3") (pin "41") (pinfunction "PE6_41") (pintype "bidirectional"))
      (node (ref "JP11") (pin "16") (pinfunction "16_16") (pintype "passive"))
      (node (ref "JP15") (pin "16") (pinfunction "16_16") (pintype "passive"))
      (node (ref "Q10") (pin "2") (pinfunction "S_2") (pintype "passive"))
      (node (ref "R51") (pin "1") (pinfunction "1_1") (pintype "passive"))
    )
    (net (code "124") (name "SCK") (class "Default")
      (node (ref "IC3") (pin "22") (pinfunction "PC7_22") (pintype "bidirectional"))
      (node (ref "JP10") (pin "22") (pinfunction "22_22") (pintype "passive"))
      (node (ref "JP14") (pin "22") (pinfunction "22_22") (pintype "passive"))
    )
    (net (code "125") (name "SCLK") (class "Default")
      (node (ref "U$2") (pin "5") (pinfunction "SCLK_5") (pintype "bidirectional"))
      (node (ref "U$6") (pin "5") (pinfunction "SCLK_5") (pintype "bidirectional"))
    )
    (net (code "126") (name "SPREAD") (class "Default")
      (node (ref "S0") (pin "22") (pinfunction "SPREAD_22") (pintype "bidirectional"))
    )
    (net (code "127") (name "SS-0") (class "Default")
      (node (ref "IC3") (pin "18") (pinfunction "PC3_18") (pintype "bidirectional"))
      (node (ref "JP10") (pin "18") (pinfunction "18_18") (pintype "passive"))
      (node (ref "JP14") (pin "18") (pinfunction "18_18") (pintype "passive"))
      (node (ref "U$2") (pin "6") (pinfunction "SCS_6") (pintype "bidirectional"))
    )
    (net (code "128") (name "SS-1") (class "Default")
      (node (ref "IC3") (pin "19") (pinfunction "PC4_19") (pintype "bidirectional"))
      (node (ref "JP10") (pin "19") (pinfunction "19_19") (pintype "passive"))
      (node (ref "JP14") (pin "19") (pinfunction "19_19") (pintype "passive"))
      (node (ref "U$6") (pin "6") (pinfunction "SCS_6") (pintype "bidirectional"))
    )
    (net (code "129") (name "START_GATE1") (class "Default")
      (node (ref "C12") (pin "1") (pinfunction "1_1") (pintype "passive"))
      (node (ref "Q3") (pin "4") (pinfunction "G_4") (pintype "passive"))
      (node (ref "Q7") (pin "3") (pinfunction "D_3") (pintype "passive"))
      (node (ref "R5") (pin "2") (pinfunction "2_2") (pintype "passive"))
      (node (ref "R6") (pin "1") (pinfunction "1_1") (pintype "passive"))
    )
    (net (code "130") (name "STEP_S0") (class "Default")
      (node (ref "S0") (pin "25") (pinfunction "STEP_25") (pintype "bidirectional"))
    )
    (net (code "131") (name "SW0") (class "Default")
      (node (ref "IC3") (pin "62") (pinfunction "PH7_62") (pintype "bidirectional"))
    )
    (net (code "132") (name "SW1") (class "Default")
      (node (ref "IC3") (pin "61") (pinfunction "PH6_61") (pintype "bidirectional"))
    )
    (net (code "133") (name "SW2") (class "Default")
      (node (ref "IC3") (pin "60") (pinfunction "PH5_60") (pintype "bidirectional"))
    )
    (net (code "134") (name "SW3") (class "Default")
      (node (ref "IC3") (pin "59") (pinfunction "PH4_59") (pintype "bidirectional"))
    )
    (net (code "135") (name "TX") (class "Default")
      (node (ref "IC3") (pin "52") (pinfunction "PF7_52") (pintype "bidirectional"))
      (node (ref "JP12") (pin "2") (pinfunction "2_2") (pintype "passive"))
      (node (ref "JP16") (pin "2") (pinfunction "2_2") (pintype "passive"))
    )
    (net (code "136") (name "TXD0") (class "Default")
      (node (ref "CH2") (pin "3") (pinfunction "RX_3") (pintype "bidirectional"))
    )
    (net (code "137") (name "TX_485") (class "Default")
      (node (ref "IC3") (pin "42") (pinfunction "PE7_42") (pintype "bidirectional"))
      (node (ref "JP11") (pin "17") (pinfunction "17_17") (pintype "passive"))
      (node (ref "JP15") (pin "17") (pinfunction "17_17") (pintype "passive"))
      (node (ref "MAX1") (pin "4") (pinfunction "DI_4") (pintype "input"))
    )
    (net (code "138") (name "VCC") (class "Default")
      (node (ref "C13") (pin "1") (pinfunction "1_1") (pintype "passive"))
      (node (ref "C14") (pin "1") (pinfunction "1_1") (pintype "passive"))
      (node (ref "C16") (pin "1") (pinfunction "1_1") (pintype "passive"))
      (node (ref "C17") (pin "+") (pinfunction "+_+") (pintype "passive"))
      (node (ref "C28") (pin "1") (pinfunction "1_1") (pintype "passive"))
      (node (ref "C29") (pin "1") (pinfunction "1_1") (pintype "passive"))
      (node (ref "C32") (pin "1") (pinfunction "1_1") (pintype "passive"))
      (node (ref "C33") (pin "1") (pinfunction "1_1") (pintype "passive"))
      (node (ref "C38") (pin "+") (pinfunction "+_+") (pintype "passive"))
      (node (ref "C39") (pin "+") (pinfunction "+_+") (pintype "passive"))
      (node (ref "Q3") (pin "5") (pinfunction "D_5") (pintype "passive"))
      (node (ref "Q3") (pin "6") (pinfunction "D_6") (pintype "passive"))
      (node (ref "Q3") (pin "7") (pinfunction "D_7") (pintype "passive"))
      (node (ref "Q3") (pin "8") (pinfunction "D_8") (pintype "passive"))
      (node (ref "R8") (pin "1") (pinfunction "1_1") (pintype "passive"))
      (node (ref "S0") (pin "14") (pinfunction "VS_14") (pintype "bidirectional"))
      (node (ref "S0") (pin "7") (pinfunction "VS_7") (pintype "bidirectional"))
      (node (ref "U$1") (pin "6") (pinfunction "VCC_6") (pintype "power_in"))
      (node (ref "U$2") (pin "13") (pinfunction "VM_13") (pintype "bidirectional"))
      (node (ref "U$2") (pin "20") (pinfunction "VM_20") (pintype "bidirectional"))
      (node (ref "U$6") (pin "13") (pinfunction "VM_13") (pintype "bidirectional"))
      (node (ref "U$6") (pin "20") (pinfunction "VM_20") (pintype "bidirectional"))
    )
    (net (code "139") (name "unconnected-(CH2-.NC-Pad8)") (class "Default")
      (node (ref "CH2") (pin "8") (pinfunction ".NC_8") (pintype "bidirectional"))
    )
    (net (code "140") (name "unconnected-(CH2-CTS-Pad9)") (class "Default")
      (node (ref "CH2") (pin "9") (pinfunction "CTS_9") (pintype "bidirectional"))
    )
    (net (code "141") (name "unconnected-(CH2-DCD-Pad12)") (class "Default")
      (node (ref "CH2") (pin "12") (pinfunction "DCD_12") (pintype "bidirectional"))
    )
    (net (code "142") (name "unconnected-(CH2-DSR-Pad10)") (class "Default")
      (node (ref "CH2") (pin "10") (pinfunction "DSR_10") (pintype "bidirectional"))
    )
    (net (code "143") (name "unconnected-(CH2-DTR-Pad13)") (class "Default")
      (node (ref "CH2") (pin "13") (pinfunction "DTR_13") (pintype "bidirectional"))
    )
    (net (code "144") (name "unconnected-(CH2-NC-Pad7)") (class "Default")
      (node (ref "CH2") (pin "7") (pinfunction "NC_7") (pintype "bidirectional"))
    )
    (net (code "145") (name "unconnected-(CH2-RI-Pad11)") (class "Default")
      (node (ref "CH2") (pin "11") (pinfunction "RI_11") (pintype "bidirectional"))
    )
    (net (code "146") (name "unconnected-(CH2-RS232-Pad15)") (class "Default")
      (node (ref "CH2") (pin "15") (pinfunction "RS232_15") (pintype "bidirectional"))
    )
    (net (code "147") (name "unconnected-(S0-INDEX-Pad2)") (class "Default")
      (node (ref "S0") (pin "2") (pinfunction "INDEX_2") (pintype "bidirectional"))
    )
    (net (code "148") (name "unconnected-(S0-VREF-Pad15)") (class "Default")
      (node (ref "S0") (pin "15") (pinfunction "VREF_15") (pintype "bidirectional"))
    )
    (net (code "149") (name "unconnected-(X4-ID-Pad4)") (class "Default")
      (node (ref "X4") (pin "4") (pinfunction "ID_4") (pintype "bidirectional"))
    )
    (net (code "150") (name "~{RESET}") (class "Default")
      (node (ref "CH2") (pin "14") (pinfunction "RTS_14") (pintype "bidirectional"))
      (node (ref "IC3") (pin "90") (pinfunction "RESET_90") (pintype "input"))
      (node (ref "JP13") (pin "15") (pinfunction "15_15") (pintype "passive"))
      (node (ref "JP17") (pin "15") (pinfunction "15_15") (pintype "passive"))
    )
  )
)
